# MotherboardRev1.net
KiCad netlist of a schematic drawn in EAGLE
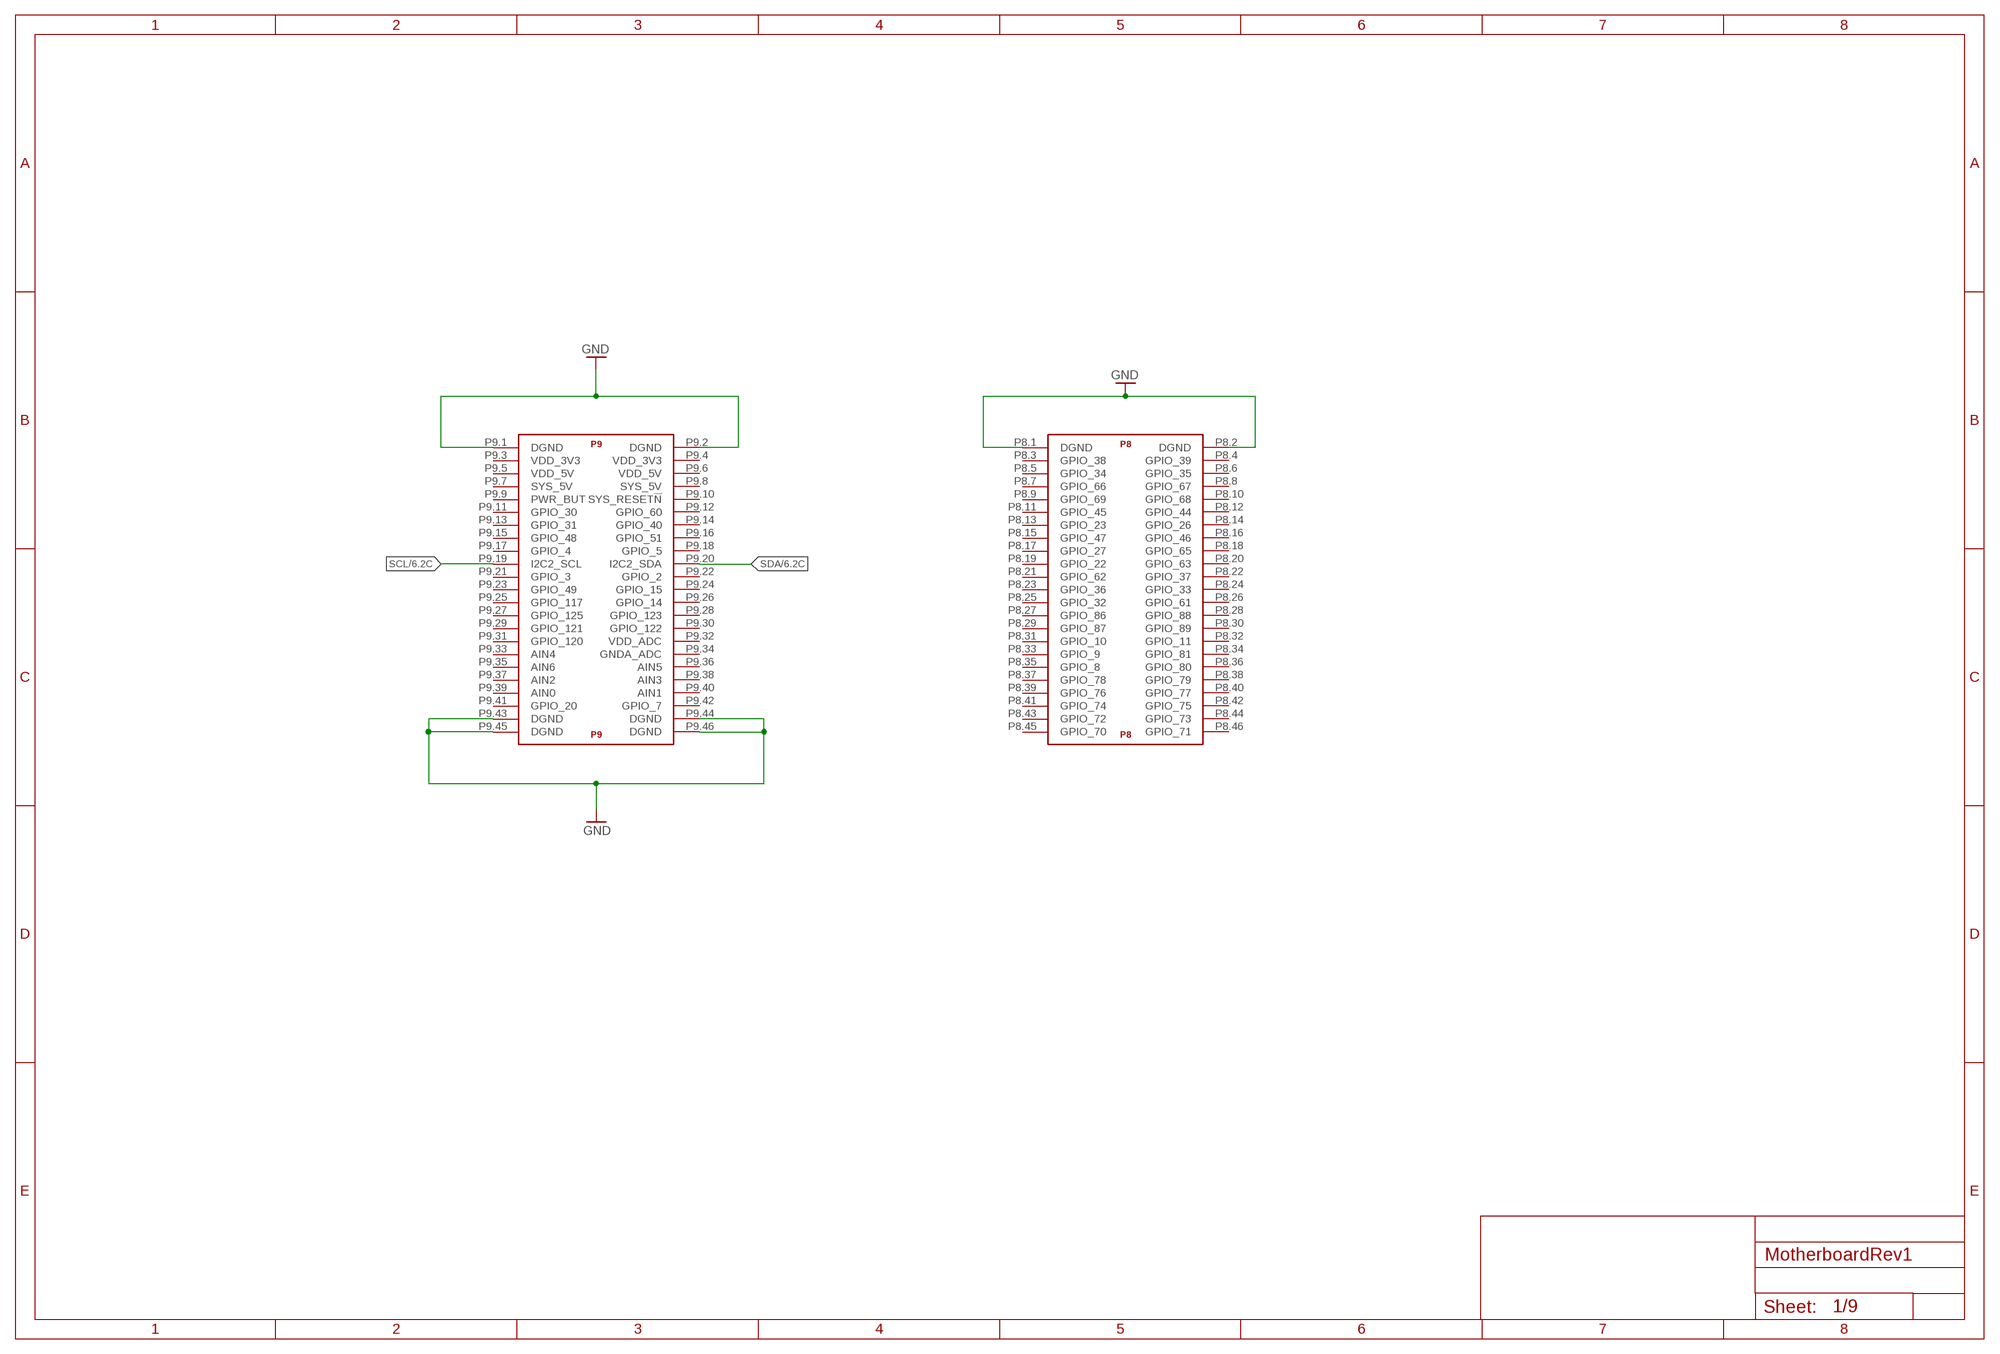
[diagram p0: schematic, sheet 1]
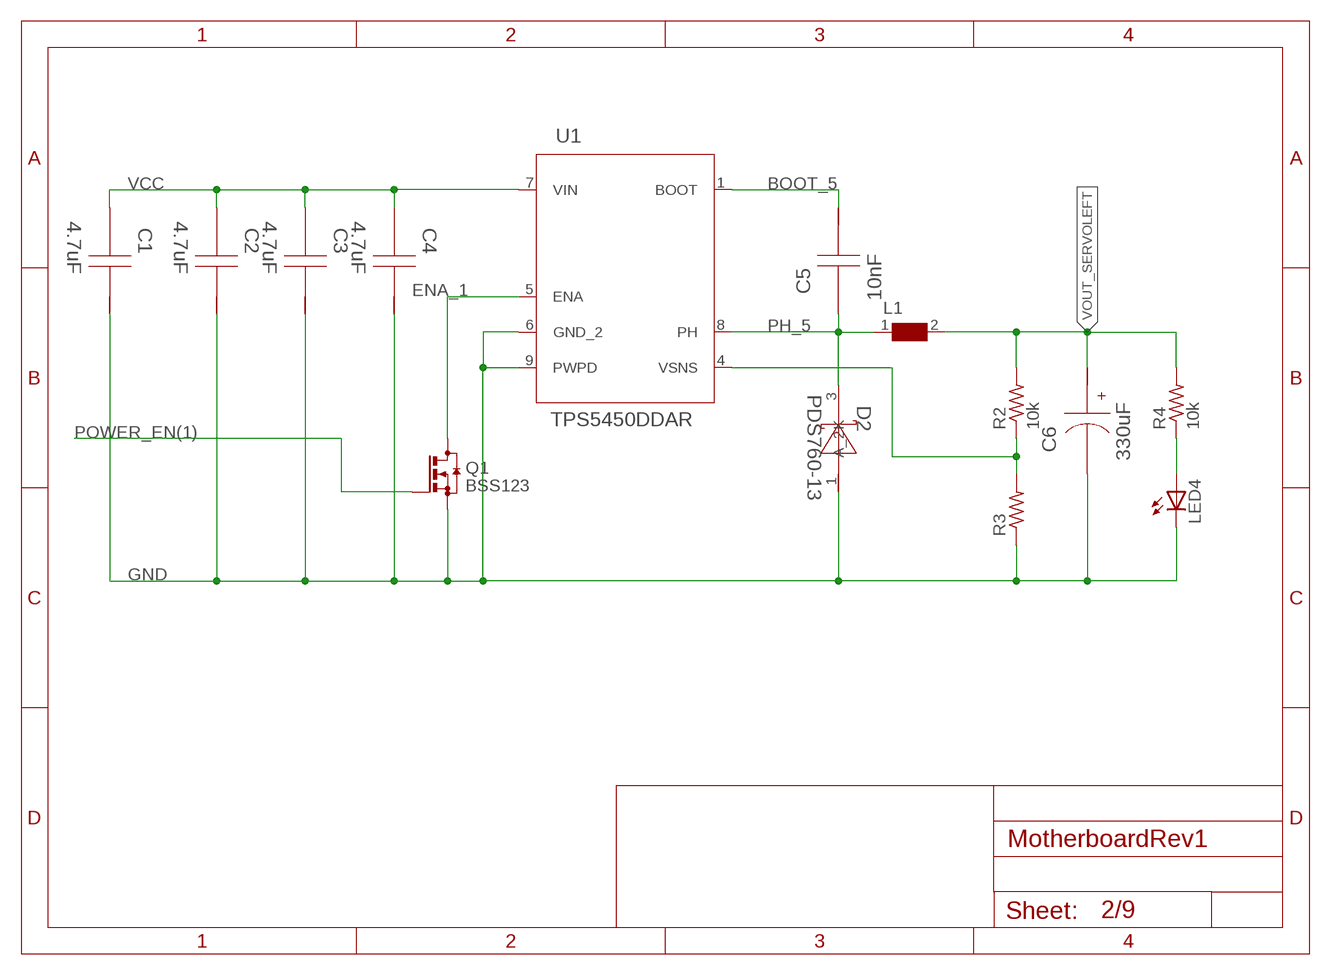
[diagram p1: schematic, sheet 2]
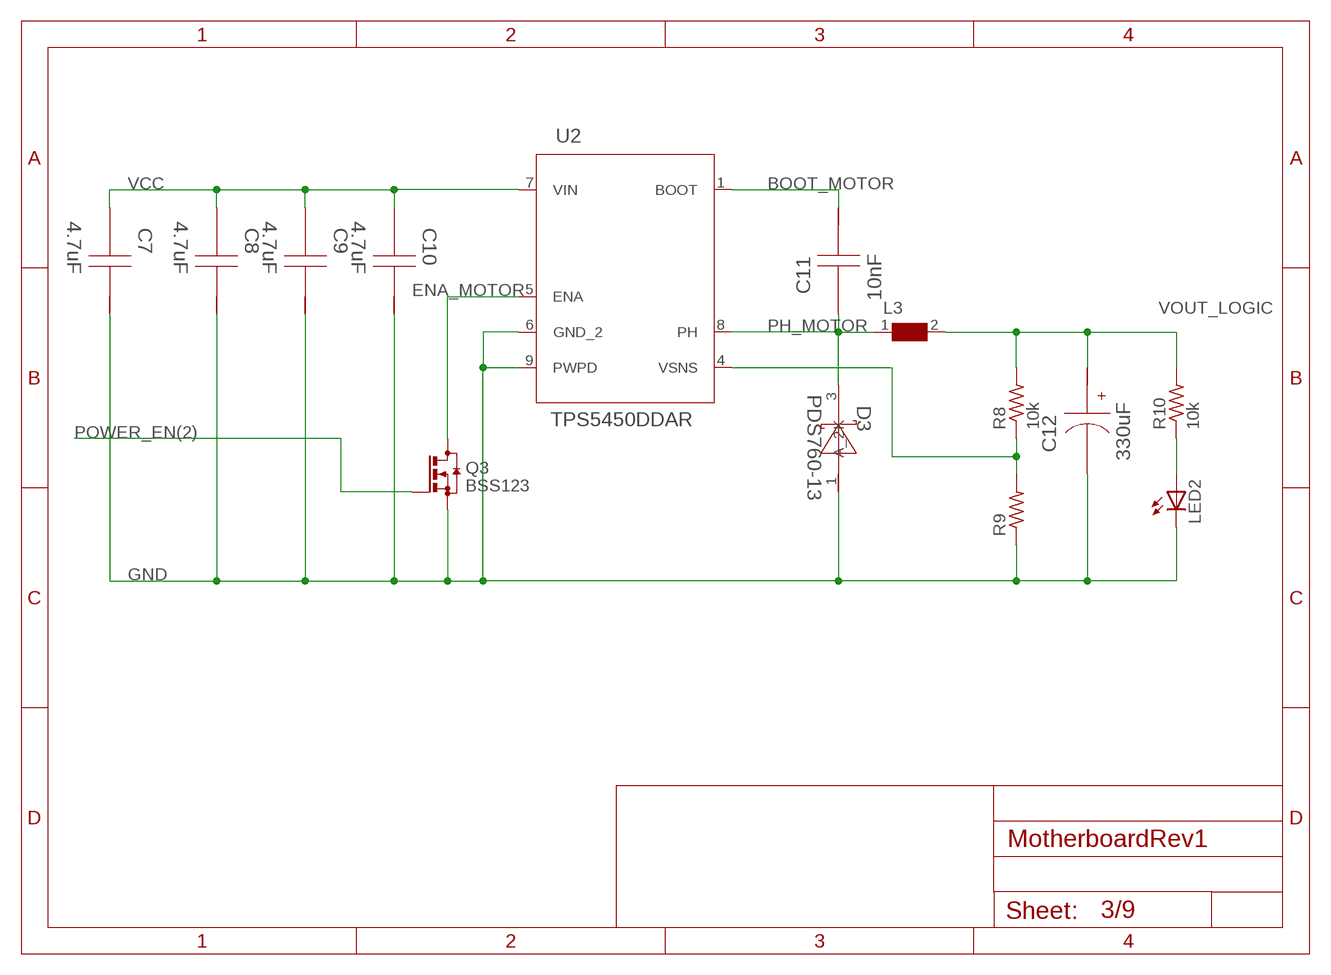
[diagram p2: schematic, sheet 3]
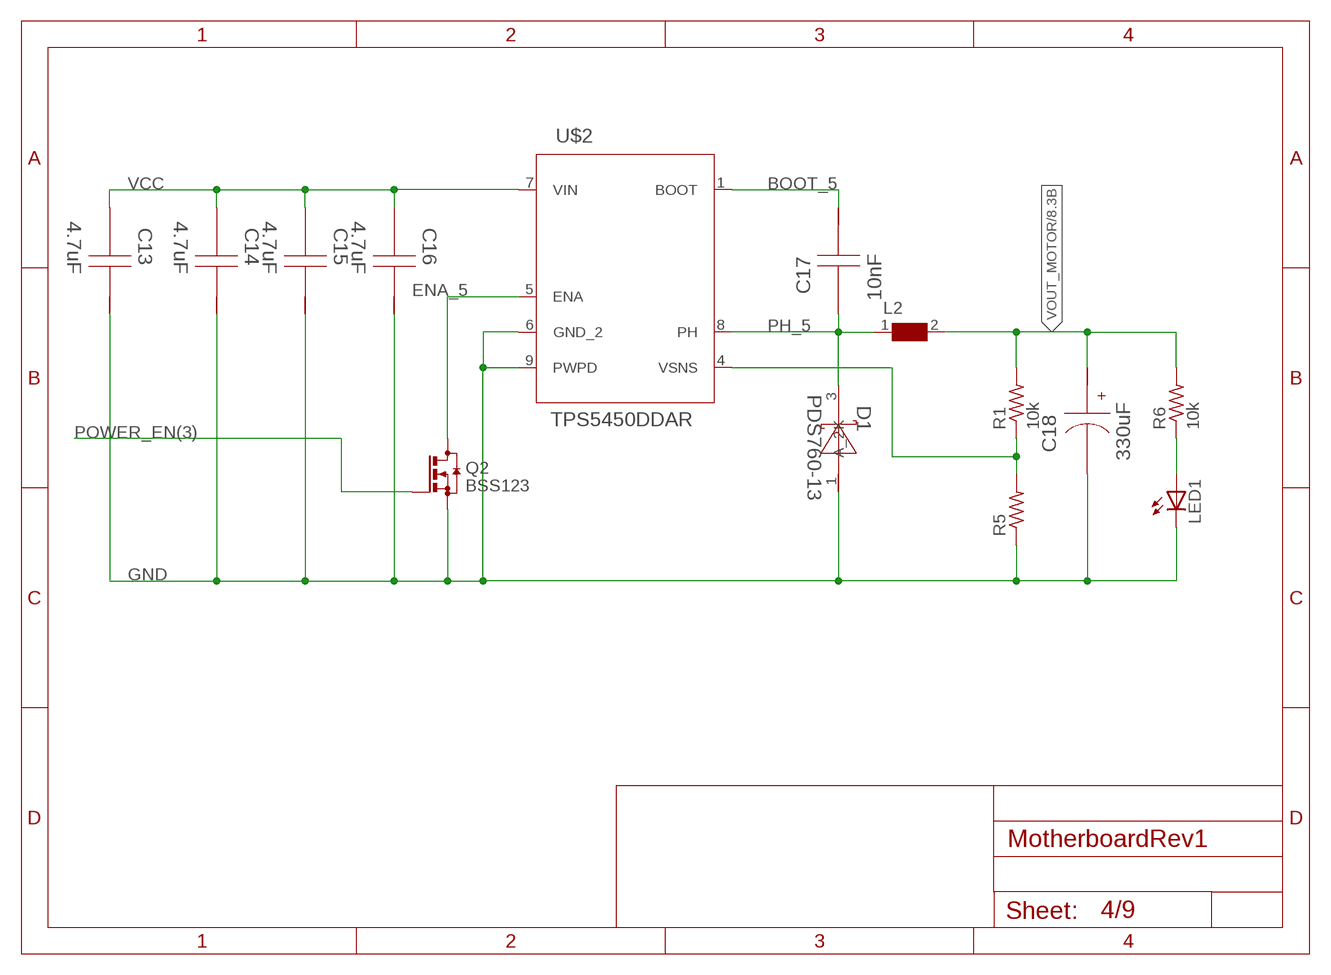
[diagram p3: schematic, sheet 4]
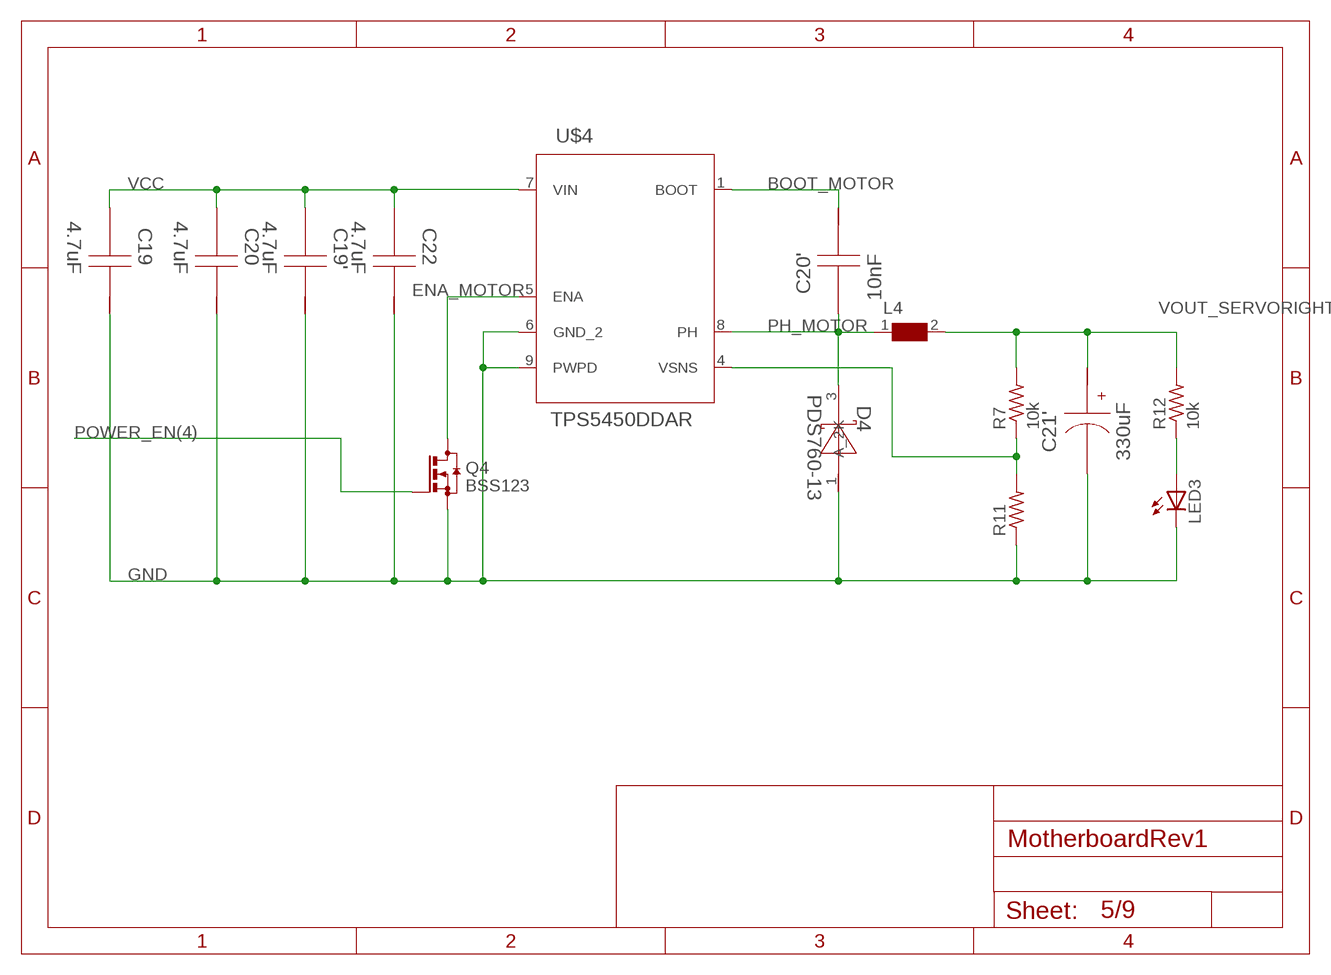
[diagram p4: schematic, sheet 5]
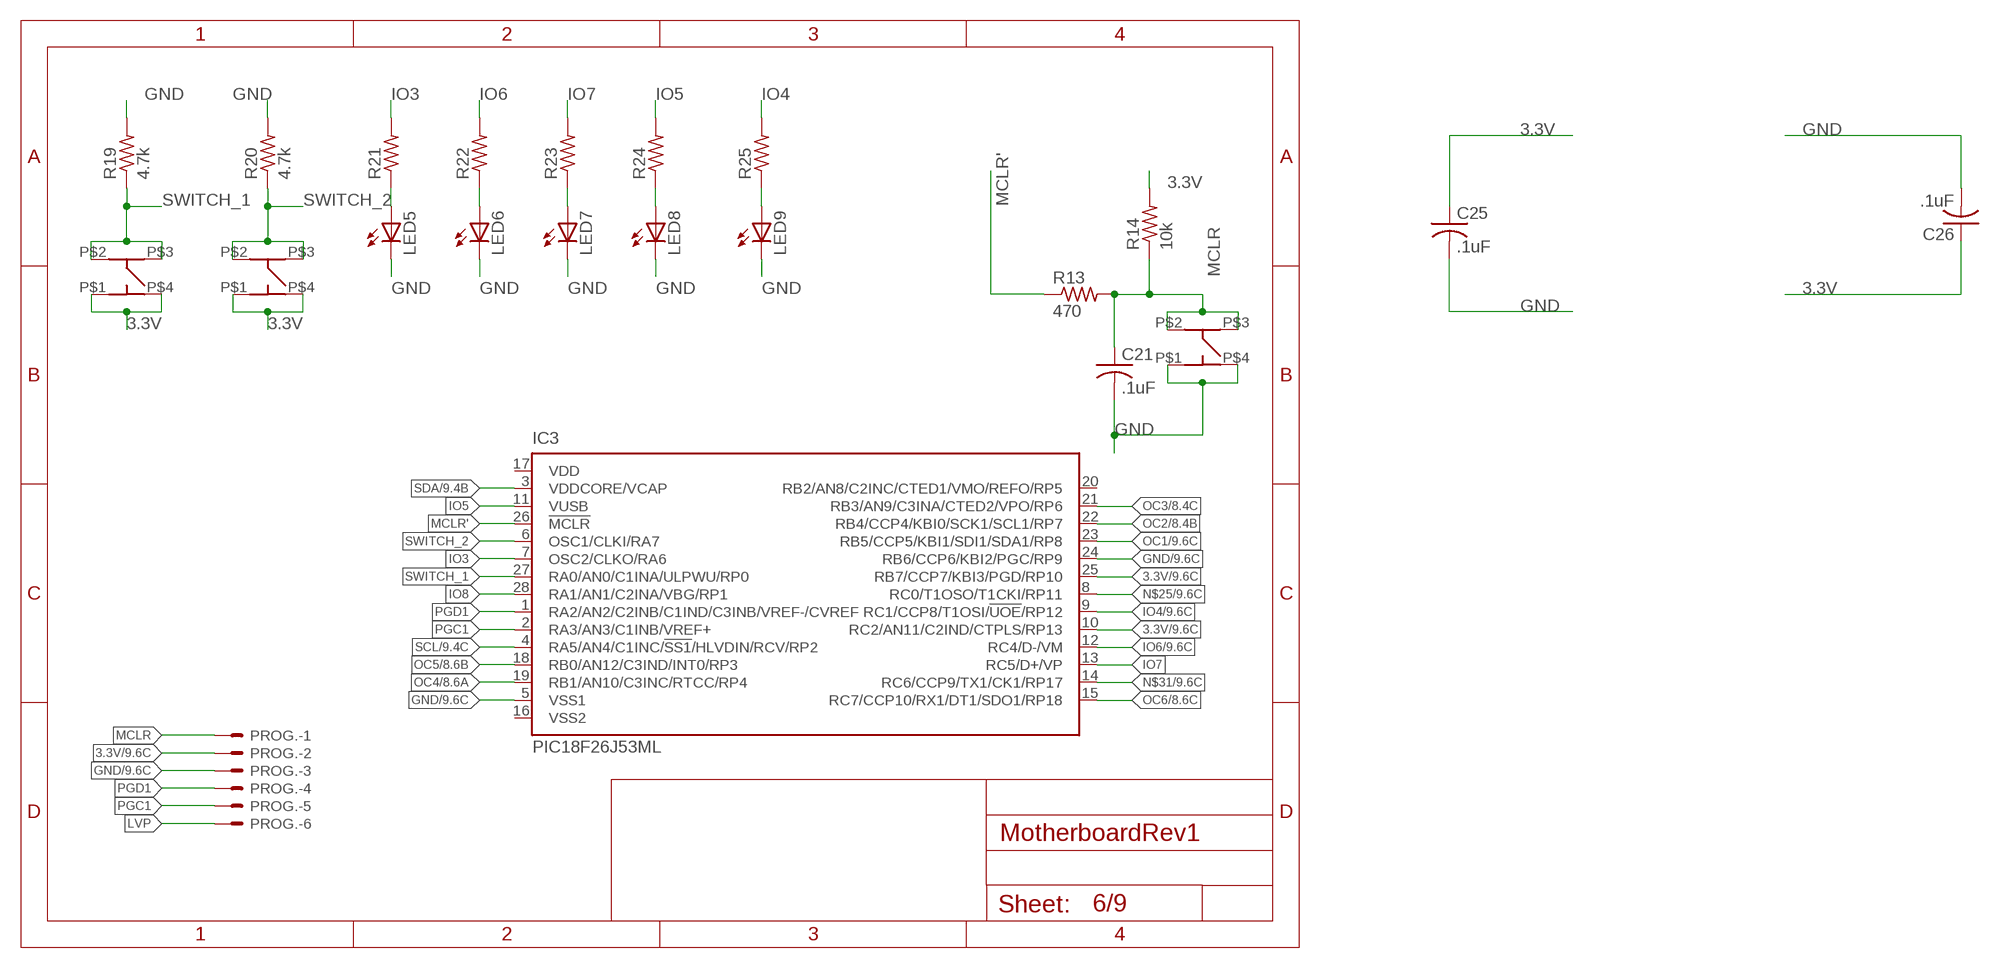
[diagram p5: schematic, sheet 6]
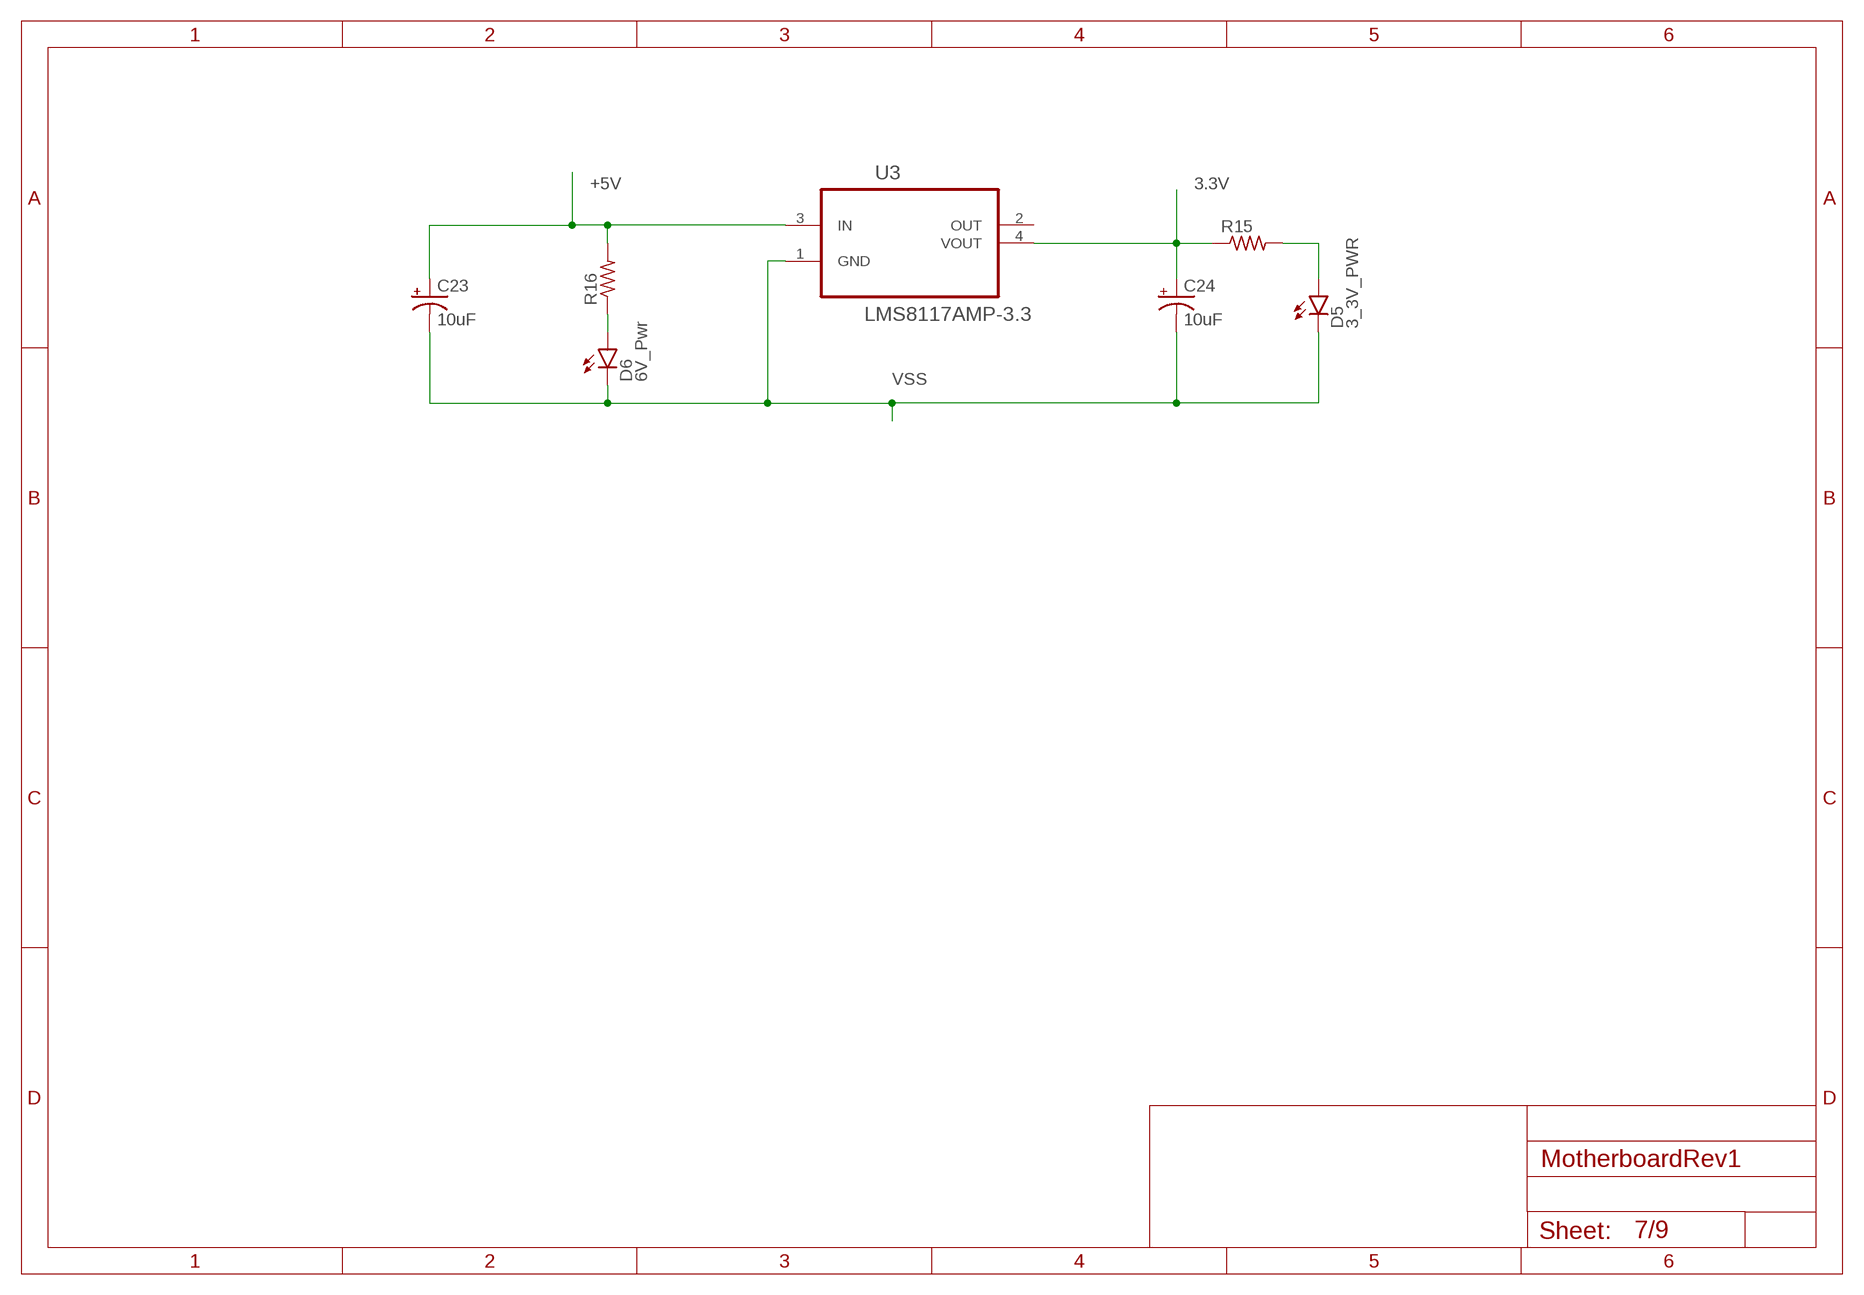
[diagram p6: schematic, sheet 7]
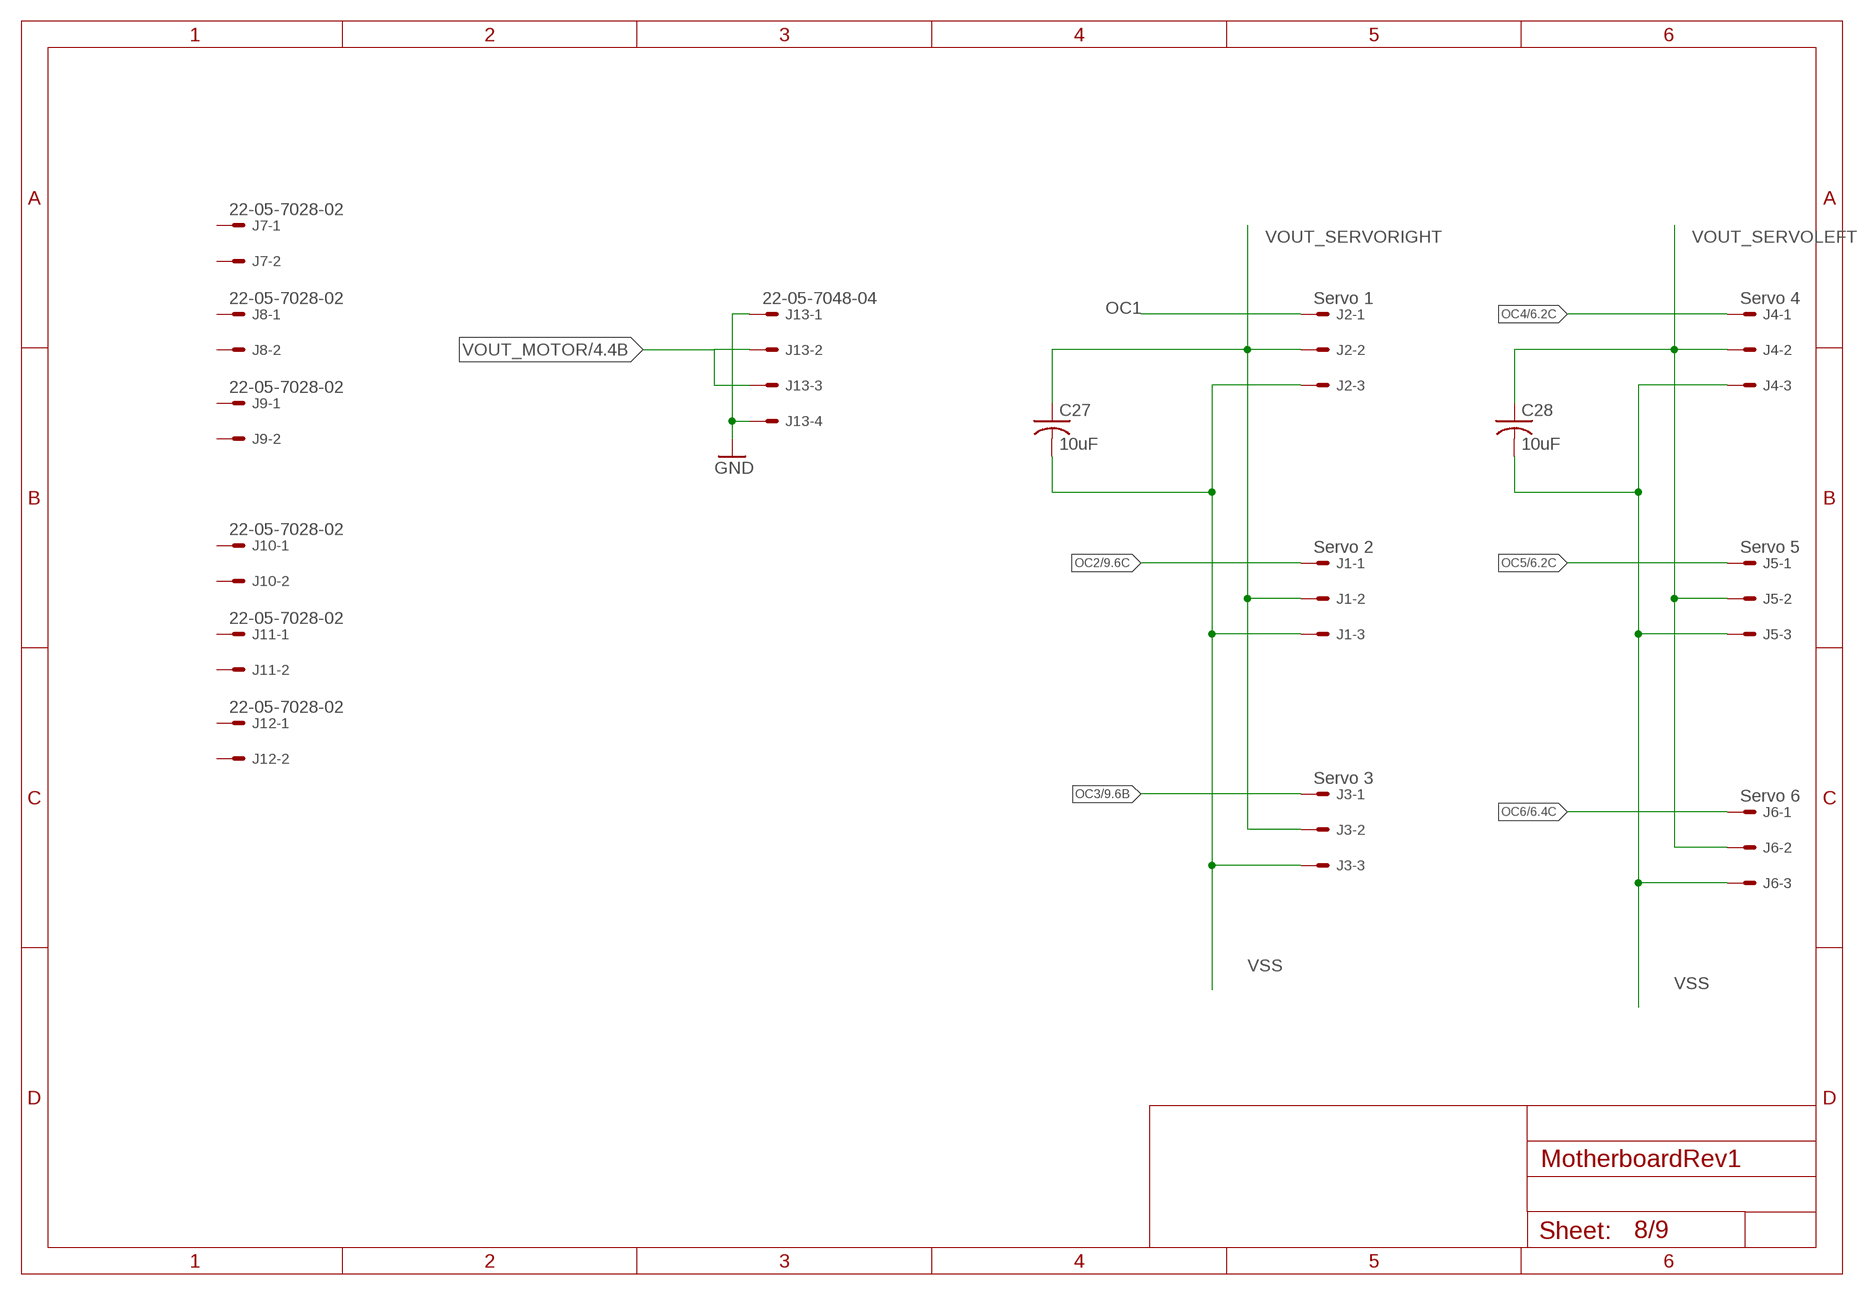
[diagram p7: schematic, sheet 8]
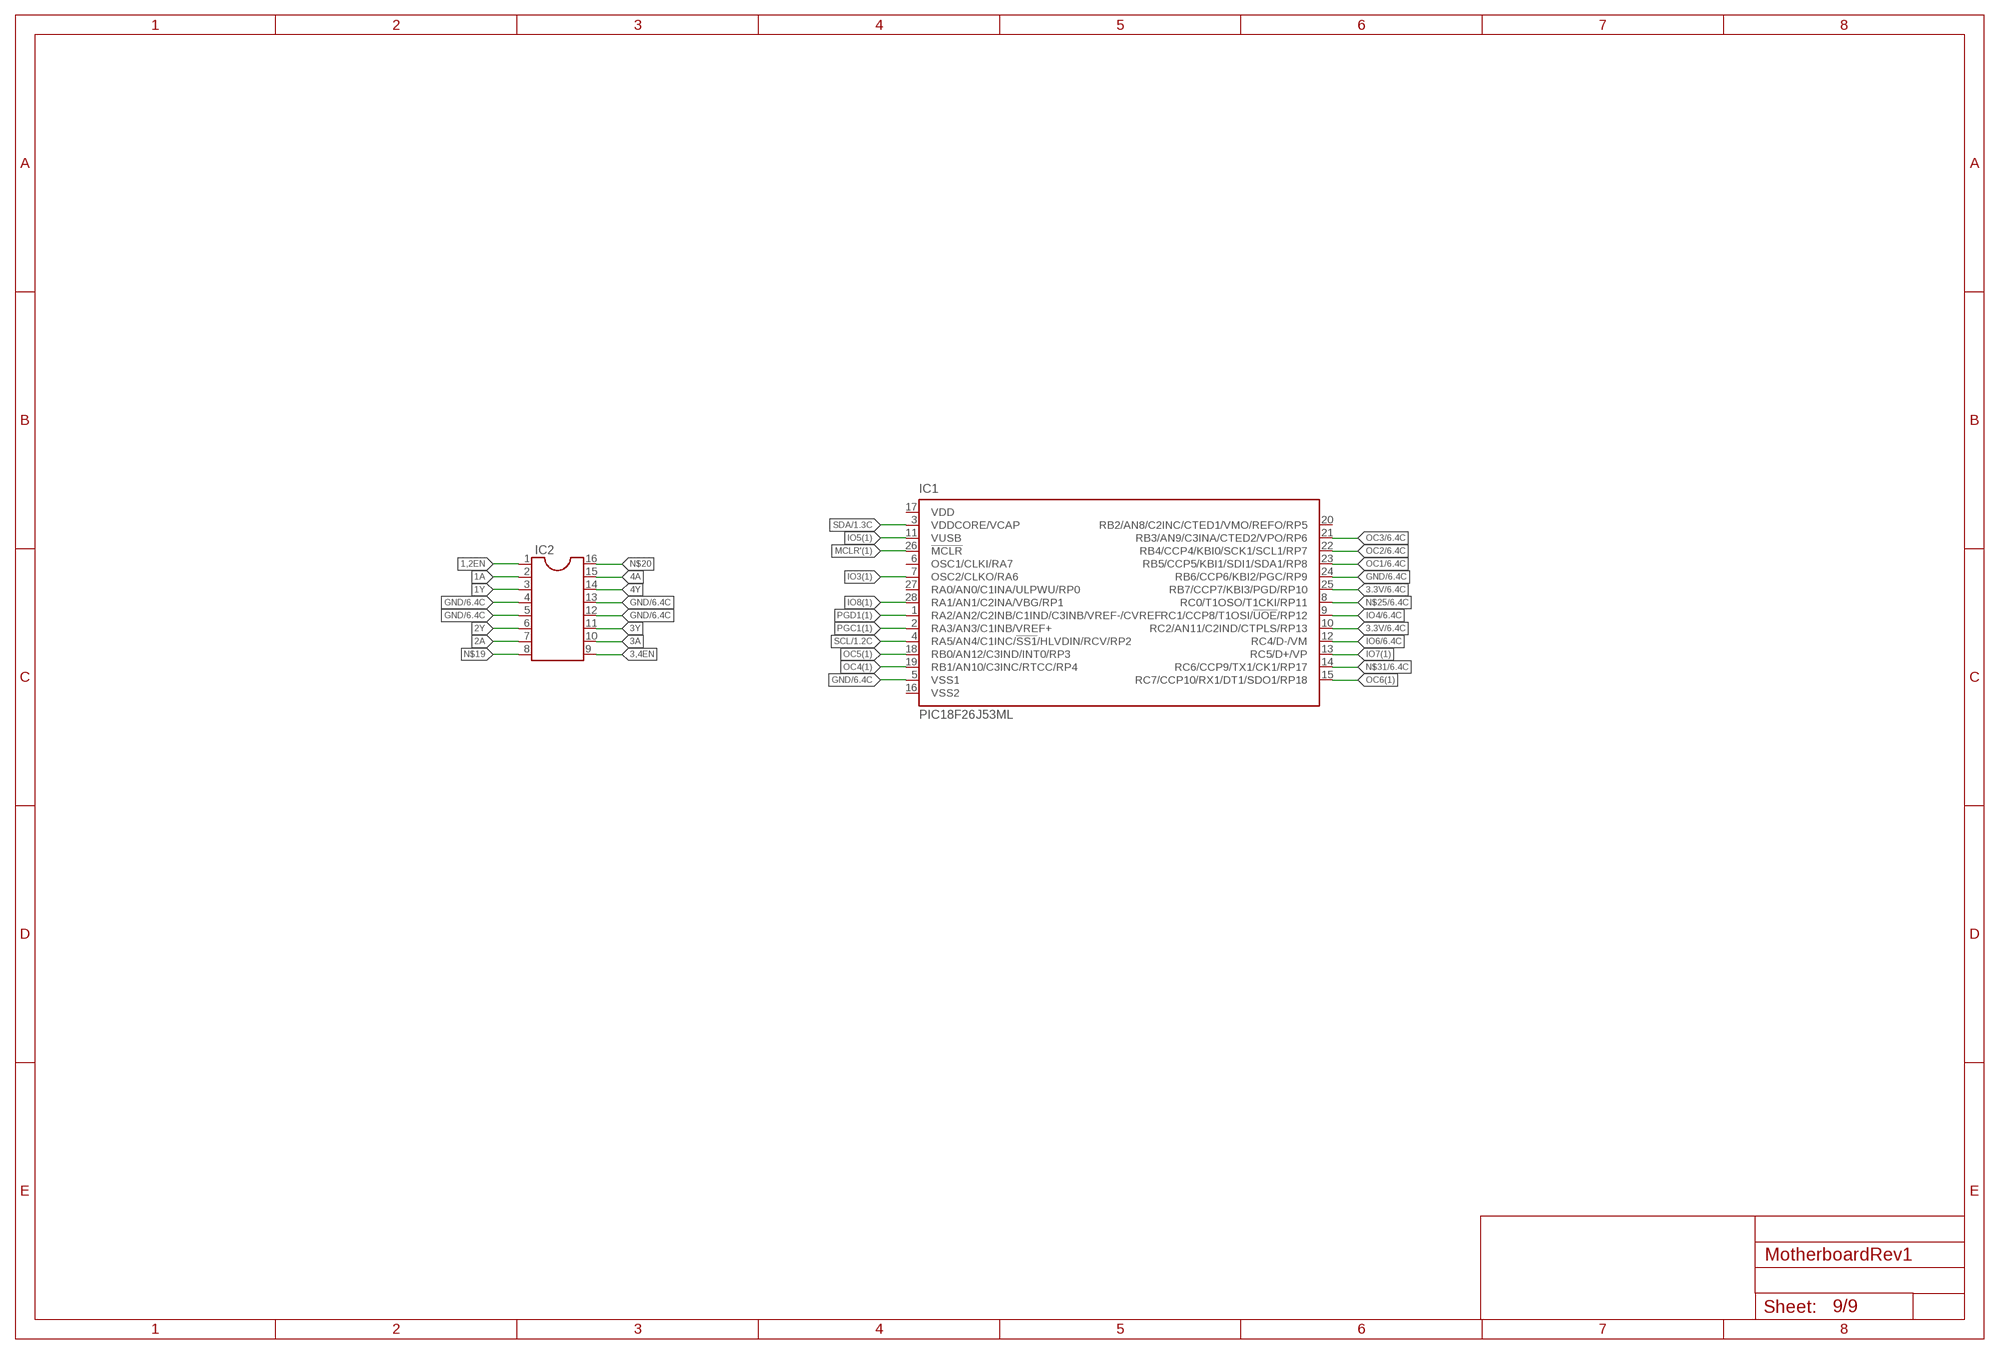
[diagram p8: schematic, sheet 9]

(export (version "E")
  (design (tool "Eeschema 10.0.6"))
  (components
    (comp (ref "C7")
      (value "4.7uF")
      (footprint "eagle-import:1206")
      (fields (field (name "MANUFACTURER_PART_NUMBER") "GRM31CR71H475KA12L"))
      (libsource (lib "eagle-import") (part "GRM31CR71H475KA12L"))
    )
    (comp (ref "C8")
      (value "4.7uF")
      (footprint "eagle-import:1206")
      (fields (field (name "MANUFACTURER_PART_NUMBER") "GRM31CR71H475KA12L"))
      (libsource (lib "eagle-import") (part "GRM31CR71H475KA12L"))
    )
    (comp (ref "C9")
      (value "4.7uF")
      (footprint "eagle-import:1206")
      (fields (field (name "MANUFACTURER_PART_NUMBER") "GRM31CR71H475KA12L"))
      (libsource (lib "eagle-import") (part "GRM31CR71H475KA12L"))
    )
    (comp (ref "C10")
      (value "4.7uF")
      (footprint "eagle-import:1206")
      (fields (field (name "MANUFACTURER_PART_NUMBER") "GRM31CR71H475KA12L"))
      (libsource (lib "eagle-import") (part "GRM31CR71H475KA12L"))
    )
    (comp (ref "C11")
      (value "10nF")
      (footprint "eagle-import:0805")
      (fields (field (name "MANUFACTURER_PART_NUMBER") "C0805C103K5RACTU"))
      (libsource (lib "eagle-import") (part "C0805C103K5RACTU"))
    )
    (comp (ref "C12")
      (value "330uF")
      (footprint "eagle-import:SM_RADIAL_10AMM")
      (fields (field (name "MANUFACTURER_PART_NUMBER") "10SVP330MX"))
      (libsource (lib "eagle-import") (part "10SVP330MX"))
    )
    (comp (ref "D3")
      (value "PDS760-13")
      (footprint "eagle-import:POWERDI5")
      (libsource (lib "eagle-import") (part "PDS760-13"))
    )
    (comp (ref "L3")
      (value "WE-HCC-7443331000_1090")
      (footprint "eagle-import:WE-HCC_1090")
      (fields (field (name "MPN") "7443331000"))
      (libsource (lib "eagle-import") (part "WE-HCC_1090-7443331000"))
    )
    (comp (ref "LED2")
      (value "LEDSML1206")
      (footprint "eagle-import:SML1206")
      (libsource (lib "eagle-import") (part "LEDSML1206"))
    )
    (comp (ref "Q3")
      (value "BSS123")
      (footprint "eagle-import:SOT23")
      (libsource (lib "eagle-import") (part "BSS123"))
    )
    (comp (ref "R8")
      (value "10k")
      (footprint "eagle-import:R1206")
      (libsource (lib "eagle-import") (part "R-US_R1206"))
    )
    (comp (ref "R9")
      (value "R-US_R1206")
      (footprint "eagle-import:R1206")
      (libsource (lib "eagle-import") (part "R-US_R1206"))
    )
    (comp (ref "R10")
      (value "10k")
      (footprint "eagle-import:R1206")
      (libsource (lib "eagle-import") (part "R-US_R1206"))
    )
    (comp (ref "U2")
      (value "TPS5450DDAR")
      (footprint "eagle-import:R-PDSO-G8")
      (fields (field (name "MANUFACTURER_PART_NUMBER") "TPS5450DDA"))
      (libsource (lib "eagle-import") (part "TPS5450DDAR"))
    )
    (comp (ref "C27")
      (value "10uF")
      (footprint "eagle-import:C0805")
      (libsource (lib "eagle-import") (part "C-USC0805"))
    )
    (comp (ref "C28")
      (value "10uF")
      (footprint "eagle-import:C0805")
      (libsource (lib "eagle-import") (part "C-USC0805"))
    )
    (comp (ref "J1")
      (value "Servo 2")
      (footprint "eagle-import:7395-03")
      (libsource (lib "eagle-import") (part "22-?-0305-7038"))
    )
    (comp (ref "J2")
      (value "Servo 1")
      (footprint "eagle-import:7395-03")
      (libsource (lib "eagle-import") (part "22-?-0305-7038"))
    )
    (comp (ref "J3")
      (value "Servo 3")
      (footprint "eagle-import:7395-03")
      (libsource (lib "eagle-import") (part "22-?-0305-7038"))
    )
    (comp (ref "J4")
      (value "Servo 4")
      (footprint "eagle-import:7395-03")
      (libsource (lib "eagle-import") (part "22-?-0305-7038"))
    )
    (comp (ref "J5")
      (value "Servo 5")
      (footprint "eagle-import:7395-03")
      (libsource (lib "eagle-import") (part "22-?-0305-7038"))
    )
    (comp (ref "J6")
      (value "Servo 6")
      (footprint "eagle-import:7395-03")
      (libsource (lib "eagle-import") (part "22-?-0305-7038"))
    )
    (comp (ref "J7")
      (value "22-05-7028-02")
      (footprint "eagle-import:7395-02")
      (libsource (lib "eagle-import") (part "22-?-0205-7028"))
    )
    (comp (ref "J8")
      (value "22-05-7028-02")
      (footprint "eagle-import:7395-02")
      (libsource (lib "eagle-import") (part "22-?-0205-7028"))
    )
    (comp (ref "J9")
      (value "22-05-7028-02")
      (footprint "eagle-import:7395-02")
      (libsource (lib "eagle-import") (part "22-?-0205-7028"))
    )
    (comp (ref "J10")
      (value "22-05-7028-02")
      (footprint "eagle-import:7395-02")
      (libsource (lib "eagle-import") (part "22-?-0205-7028"))
    )
    (comp (ref "J11")
      (value "22-05-7028-02")
      (footprint "eagle-import:7395-02")
      (libsource (lib "eagle-import") (part "22-?-0205-7028"))
    )
    (comp (ref "J12")
      (value "22-05-7028-02")
      (footprint "eagle-import:7395-02")
      (libsource (lib "eagle-import") (part "22-?-0205-7028"))
    )
    (comp (ref "J13")
      (value "22-05-7048-04")
      (footprint "eagle-import:7395-04")
      (libsource (lib "eagle-import") (part "22-?-0405-7048"))
    )
    (comp (ref "C23")
      (value "10uF")
      (footprint "eagle-import:EIA3216")
      (libsource (lib "eagle-import") (part "10UF-16V-10%(TANT)"))
    )
    (comp (ref "C24")
      (value "10uF")
      (footprint "eagle-import:EIA3216")
      (libsource (lib "eagle-import") (part "10UF-16V-10%(TANT)"))
    )
    (comp (ref "D5")
      (value "3_3V_PWR")
      (footprint "eagle-import:FKIT-LED-1206")
      (libsource (lib "eagle-import") (part "LED-FKIT-1206"))
    )
    (comp (ref "D6")
      (value "6V_Pwr")
      (footprint "eagle-import:FKIT-LED-1206")
      (libsource (lib "eagle-import") (part "LED-FKIT-1206"))
    )
    (comp (ref "R15")
      (value "R-US_R0805W")
      (footprint "eagle-import:R0805W")
      (libsource (lib "eagle-import") (part "R-US_R0805W"))
    )
    (comp (ref "R16")
      (value "R-US_R0805W")
      (footprint "eagle-import:R0805W")
      (libsource (lib "eagle-import") (part "R-US_R0805W"))
    )
    (comp (ref "U3")
      (value "LMS8117AMP-3.3")
      (footprint "eagle-import:SOT230P696X180-4N")
      (libsource (lib "eagle-import") (part "LMS8117AMP-3.3"))
    )
    (comp (ref "C21")
      (value ".1uF")
      (footprint "eagle-import:C0805")
      (libsource (lib "eagle-import") (part "C-USC0805"))
    )
    (comp (ref "C25")
      (value ".1uF")
      (footprint "eagle-import:C0805")
      (libsource (lib "eagle-import") (part "C-USC0805"))
    )
    (comp (ref "C26")
      (value ".1uF")
      (footprint "eagle-import:C0805")
      (libsource (lib "eagle-import") (part "C-USC0805"))
    )
    (comp (ref "IC3")
      (value "PIC18F26J53ML")
      (footprint "eagle-import:QFN28-ML_6X6MM")
      (fields (field (name "MPN") "PIC18F26J53-I/ML"))
      (libsource (lib "eagle-import") (part "PIC18F2J53ML6"))
    )
    (comp (ref "LED5")
      (value "LED_LEDCHIPLED_1206")
      (footprint "eagle-import:LED_CHIPLED_1206")
      (libsource (lib "eagle-import") (part "LED_LEDCHIPLED_1206"))
    )
    (comp (ref "LED6")
      (value "LED_LEDCHIPLED_1206")
      (footprint "eagle-import:LED_CHIPLED_1206")
      (libsource (lib "eagle-import") (part "LED_LEDCHIPLED_1206"))
    )
    (comp (ref "LED7")
      (value "LED_LEDCHIPLED_1206")
      (footprint "eagle-import:LED_CHIPLED_1206")
      (libsource (lib "eagle-import") (part "LED_LEDCHIPLED_1206"))
    )
    (comp (ref "LED8")
      (value "LED_LEDCHIPLED_1206")
      (footprint "eagle-import:LED_CHIPLED_1206")
      (libsource (lib "eagle-import") (part "LED_LEDCHIPLED_1206"))
    )
    (comp (ref "LED9")
      (value "LED_LEDCHIPLED_1206")
      (footprint "eagle-import:LED_CHIPLED_1206")
      (libsource (lib "eagle-import") (part "LED_LEDCHIPLED_1206"))
    )
    (comp (ref "PROG.")
      (value "22-23-2061")
      (footprint "eagle-import:22-23-2061")
      (fields (field (name "MF") "MOLEX"))
      (libsource (lib "eagle-import") (part "22-23-2061"))
    )
    (comp (ref "R13")
      (value "470")
      (footprint "eagle-import:R0805")
      (libsource (lib "eagle-import") (part "R-US_R0805"))
    )
    (comp (ref "R14")
      (value "10k")
      (footprint "eagle-import:R0805")
      (libsource (lib "eagle-import") (part "R-US_R0805"))
    )
    (comp (ref "R19")
      (value "4.7k")
      (footprint "eagle-import:R0805")
      (libsource (lib "eagle-import") (part "R-US_R0805"))
    )
    (comp (ref "R20")
      (value "4.7k")
      (footprint "eagle-import:R0805")
      (libsource (lib "eagle-import") (part "R-US_R0805"))
    )
    (comp (ref "R21")
      (value "R-US_M0805")
      (footprint "eagle-import:M0805")
      (libsource (lib "eagle-import") (part "R-US_M0805"))
    )
    (comp (ref "R22")
      (value "R-US_M0805")
      (footprint "eagle-import:M0805")
      (libsource (lib "eagle-import") (part "R-US_M0805"))
    )
    (comp (ref "R23")
      (value "R-US_M0805")
      (footprint "eagle-import:M0805")
      (libsource (lib "eagle-import") (part "R-US_M0805"))
    )
    (comp (ref "R24")
      (value "R-US_M0805")
      (footprint "eagle-import:M0805")
      (libsource (lib "eagle-import") (part "R-US_M0805"))
    )
    (comp (ref "R25")
      (value "R-US_M0805")
      (footprint "eagle-import:M0805")
      (libsource (lib "eagle-import") (part "R-US_M0805"))
    )
    (comp (ref "U$5")
      (value "Switch3")
      (footprint "eagle-import:MC32882_FINAL")
      (libsource (lib "eagle-import") (part "MC32882_SW"))
    )
    (comp (ref "U$6")
      (value "Switch1")
      (footprint "eagle-import:MC32882_FINAL")
      (libsource (lib "eagle-import") (part "MC32882_SW"))
    )
    (comp (ref "U$7")
      (value "Switch2")
      (footprint "eagle-import:MC32882_FINAL")
      (libsource (lib "eagle-import") (part "MC32882_SW"))
    )
    (comp (ref "U$1")
      (value "BEAGLE_BONE_BLACK_CAPE")
      (footprint "eagle-import:BEAGLE_BONE_BLACK_CAPE")
      (libsource (lib "eagle-import") (part "BEAGLE_BONE_BLACK_CAPE"))
    )
    (comp (ref "C19")
      (value "4.7uF")
      (footprint "eagle-import:1206")
      (fields (field (name "MANUFACTURER_PART_NUMBER") "GRM31CR71H475KA12L"))
      (libsource (lib "eagle-import") (part "GRM31CR71H475KA12L"))
    )
    (comp (ref "C19'")
      (value "4.7uF")
      (footprint "eagle-import:1206")
      (fields (field (name "MANUFACTURER_PART_NUMBER") "GRM31CR71H475KA12L"))
      (libsource (lib "eagle-import") (part "GRM31CR71H475KA12L"))
    )
    (comp (ref "C20")
      (value "4.7uF")
      (footprint "eagle-import:1206")
      (fields (field (name "MANUFACTURER_PART_NUMBER") "GRM31CR71H475KA12L"))
      (libsource (lib "eagle-import") (part "GRM31CR71H475KA12L"))
    )
    (comp (ref "C20'")
      (value "10nF")
      (footprint "eagle-import:0805")
      (fields (field (name "MANUFACTURER_PART_NUMBER") "C0805C103K5RACTU"))
      (libsource (lib "eagle-import") (part "C0805C103K5RACTU"))
    )
    (comp (ref "C21'")
      (value "330uF")
      (footprint "eagle-import:SM_RADIAL_10AMM")
      (fields (field (name "MANUFACTURER_PART_NUMBER") "10SVP330MX"))
      (libsource (lib "eagle-import") (part "10SVP330MX"))
    )
    (comp (ref "C22")
      (value "4.7uF")
      (footprint "eagle-import:1206")
      (fields (field (name "MANUFACTURER_PART_NUMBER") "GRM31CR71H475KA12L"))
      (libsource (lib "eagle-import") (part "GRM31CR71H475KA12L"))
    )
    (comp (ref "D4")
      (value "PDS760-13")
      (footprint "eagle-import:POWERDI5")
      (libsource (lib "eagle-import") (part "PDS760-13"))
    )
    (comp (ref "L4")
      (value "WE-HCC-7443331000_1090")
      (footprint "eagle-import:WE-HCC_1090")
      (fields (field (name "MPN") "7443331000"))
      (libsource (lib "eagle-import") (part "WE-HCC_1090-7443331000"))
    )
    (comp (ref "LED3")
      (value "LEDSML1206")
      (footprint "eagle-import:SML1206")
      (libsource (lib "eagle-import") (part "LEDSML1206"))
    )
    (comp (ref "Q4")
      (value "BSS123")
      (footprint "eagle-import:SOT23")
      (libsource (lib "eagle-import") (part "BSS123"))
    )
    (comp (ref "R7")
      (value "10k")
      (footprint "eagle-import:R1206")
      (libsource (lib "eagle-import") (part "R-US_R1206"))
    )
    (comp (ref "R11")
      (value "R-US_R1206")
      (footprint "eagle-import:R1206")
      (libsource (lib "eagle-import") (part "R-US_R1206"))
    )
    (comp (ref "R12")
      (value "10k")
      (footprint "eagle-import:R1206")
      (libsource (lib "eagle-import") (part "R-US_R1206"))
    )
    (comp (ref "U$4")
      (value "TPS5450DDAR")
      (footprint "eagle-import:R-PDSO-G8")
      (fields (field (name "MANUFACTURER_PART_NUMBER") "TPS5450DDA"))
      (libsource (lib "eagle-import") (part "TPS5450DDAR"))
    )
    (comp (ref "IC1")
      (value "PIC18F26J53ML")
      (footprint "eagle-import:QFN28-ML_6X6MM")
      (fields (field (name "MPN") "PIC18F26J53-I/ML"))
      (libsource (lib "eagle-import") (part "PIC18F2J53ML6"))
    )
    (comp (ref "IC2")
      (value "DIL16")
      (footprint "eagle-import:DIL16")
      (libsource (lib "eagle-import") (part "DIL16"))
    )
    (comp (ref "C13")
      (value "4.7uF")
      (footprint "eagle-import:1206")
      (fields (field (name "MANUFACTURER_PART_NUMBER") "GRM31CR71H475KA12L"))
      (libsource (lib "eagle-import") (part "GRM31CR71H475KA12L"))
    )
    (comp (ref "C14")
      (value "4.7uF")
      (footprint "eagle-import:1206")
      (fields (field (name "MANUFACTURER_PART_NUMBER") "GRM31CR71H475KA12L"))
      (libsource (lib "eagle-import") (part "GRM31CR71H475KA12L"))
    )
    (comp (ref "C15")
      (value "4.7uF")
      (footprint "eagle-import:1206")
      (fields (field (name "MANUFACTURER_PART_NUMBER") "GRM31CR71H475KA12L"))
      (libsource (lib "eagle-import") (part "GRM31CR71H475KA12L"))
    )
    (comp (ref "C16")
      (value "4.7uF")
      (footprint "eagle-import:1206")
      (fields (field (name "MANUFACTURER_PART_NUMBER") "GRM31CR71H475KA12L"))
      (libsource (lib "eagle-import") (part "GRM31CR71H475KA12L"))
    )
    (comp (ref "C17")
      (value "10nF")
      (footprint "eagle-import:0805")
      (fields (field (name "MANUFACTURER_PART_NUMBER") "C0805C103K5RACTU"))
      (libsource (lib "eagle-import") (part "C0805C103K5RACTU"))
    )
    (comp (ref "C18")
      (value "330uF")
      (footprint "eagle-import:SM_RADIAL_10AMM")
      (fields (field (name "MANUFACTURER_PART_NUMBER") "10SVP330MX"))
      (libsource (lib "eagle-import") (part "10SVP330MX"))
    )
    (comp (ref "D1")
      (value "PDS760-13")
      (footprint "eagle-import:POWERDI5")
      (libsource (lib "eagle-import") (part "PDS760-13"))
    )
    (comp (ref "L2")
      (value "WE-HCC-7443331000_1090")
      (footprint "eagle-import:WE-HCC_1090")
      (fields (field (name "MPN") "7443331000"))
      (libsource (lib "eagle-import") (part "WE-HCC_1090-7443331000"))
    )
    (comp (ref "LED1")
      (value "LEDSML1206")
      (footprint "eagle-import:SML1206")
      (libsource (lib "eagle-import") (part "LEDSML1206"))
    )
    (comp (ref "Q2")
      (value "BSS123")
      (footprint "eagle-import:SOT23")
      (libsource (lib "eagle-import") (part "BSS123"))
    )
    (comp (ref "R1")
      (value "10k")
      (footprint "eagle-import:R1206")
      (libsource (lib "eagle-import") (part "R-US_R1206"))
    )
    (comp (ref "R5")
      (value "R-US_R1206")
      (footprint "eagle-import:R1206")
      (libsource (lib "eagle-import") (part "R-US_R1206"))
    )
    (comp (ref "R6")
      (value "10k")
      (footprint "eagle-import:R1206")
      (libsource (lib "eagle-import") (part "R-US_R1206"))
    )
    (comp (ref "U$2")
      (value "TPS5450DDAR")
      (footprint "eagle-import:R-PDSO-G8")
      (fields (field (name "MANUFACTURER_PART_NUMBER") "TPS5450DDA"))
      (libsource (lib "eagle-import") (part "TPS5450DDAR"))
    )
    (comp (ref "C1")
      (value "4.7uF")
      (footprint "eagle-import:1206")
      (fields (field (name "MANUFACTURER_PART_NUMBER") "GRM31CR71H475KA12L"))
      (libsource (lib "eagle-import") (part "GRM31CR71H475KA12L"))
    )
    (comp (ref "C2")
      (value "4.7uF")
      (footprint "eagle-import:1206")
      (fields (field (name "MANUFACTURER_PART_NUMBER") "GRM31CR71H475KA12L"))
      (libsource (lib "eagle-import") (part "GRM31CR71H475KA12L"))
    )
    (comp (ref "C3")
      (value "4.7uF")
      (footprint "eagle-import:1206")
      (fields (field (name "MANUFACTURER_PART_NUMBER") "GRM31CR71H475KA12L"))
      (libsource (lib "eagle-import") (part "GRM31CR71H475KA12L"))
    )
    (comp (ref "C4")
      (value "4.7uF")
      (footprint "eagle-import:1206")
      (fields (field (name "MANUFACTURER_PART_NUMBER") "GRM31CR71H475KA12L"))
      (libsource (lib "eagle-import") (part "GRM31CR71H475KA12L"))
    )
    (comp (ref "C5")
      (value "10nF")
      (footprint "eagle-import:0805")
      (fields (field (name "MANUFACTURER_PART_NUMBER") "C0805C103K5RACTU"))
      (libsource (lib "eagle-import") (part "C0805C103K5RACTU"))
    )
    (comp (ref "C6")
      (value "330uF")
      (footprint "eagle-import:SM_RADIAL_10AMM")
      (fields (field (name "MANUFACTURER_PART_NUMBER") "10SVP330MX"))
      (libsource (lib "eagle-import") (part "10SVP330MX"))
    )
    (comp (ref "D2")
      (value "PDS760-13")
      (footprint "eagle-import:POWERDI5")
      (libsource (lib "eagle-import") (part "PDS760-13"))
    )
    (comp (ref "L1")
      (value "WE-HCC-7443331000_1090")
      (footprint "eagle-import:WE-HCC_1090")
      (fields (field (name "MPN") "7443331000"))
      (libsource (lib "eagle-import") (part "WE-HCC_1090-7443331000"))
    )
    (comp (ref "LED4")
      (value "LEDSML1206")
      (footprint "eagle-import:SML1206")
      (libsource (lib "eagle-import") (part "LEDSML1206"))
    )
    (comp (ref "Q1")
      (value "BSS123")
      (footprint "eagle-import:SOT23")
      (libsource (lib "eagle-import") (part "BSS123"))
    )
    (comp (ref "R2")
      (value "10k")
      (footprint "eagle-import:R1206")
      (libsource (lib "eagle-import") (part "R-US_R1206"))
    )
    (comp (ref "R3")
      (value "R-US_R1206")
      (footprint "eagle-import:R1206")
      (libsource (lib "eagle-import") (part "R-US_R1206"))
    )
    (comp (ref "R4")
      (value "10k")
      (footprint "eagle-import:R1206")
      (libsource (lib "eagle-import") (part "R-US_R1206"))
    )
    (comp (ref "U1")
      (value "TPS5450DDAR")
      (footprint "eagle-import:R-PDSO-G8")
      (fields (field (name "MANUFACTURER_PART_NUMBER") "TPS5450DDA"))
      (libsource (lib "eagle-import") (part "TPS5450DDAR"))
    )
  )
  (nets
    (net (code "1") (name "+5V") (class "Default")
      (node (ref "C23") (pin "A") (pinfunction "+_A") (pintype "passive"))
      (node (ref "R16") (pin "2") (pinfunction "2_2") (pintype "passive"))
      (node (ref "U3") (pin "3") (pinfunction "IN_3") (pintype "power_in"))
    )
    (net (code "2") (name "1,2EN") (class "Default")
      (node (ref "IC2") (pin "1") (pinfunction "1_1") (pintype "passive"))
    )
    (net (code "3") (name "1A") (class "Default")
      (node (ref "IC2") (pin "2") (pinfunction "2_2") (pintype "passive"))
    )
    (net (code "4") (name "1Y") (class "Default")
      (node (ref "IC2") (pin "3") (pinfunction "3_3") (pintype "passive"))
    )
    (net (code "5") (name "2A") (class "Default")
      (node (ref "IC2") (pin "7") (pinfunction "7_7") (pintype "passive"))
    )
    (net (code "6") (name "2Y") (class "Default")
      (node (ref "IC2") (pin "6") (pinfunction "6_6") (pintype "passive"))
    )
    (net (code "7") (name "3,4EN") (class "Default")
      (node (ref "IC2") (pin "9") (pinfunction "9_9") (pintype "passive"))
    )
    (net (code "8") (name "3.3V") (class "Default")
      (node (ref "C24") (pin "A") (pinfunction "+_A") (pintype "passive"))
      (node (ref "C25") (pin "1") (pinfunction "1_1") (pintype "passive"))
      (node (ref "C26") (pin "1") (pinfunction "1_1") (pintype "passive"))
      (node (ref "IC1") (pin "10") (pinfunction "RC2/AN11/C2IND/CTPLS/RP13_10") (pintype "bidirectional"))
      (node (ref "IC1") (pin "25") (pinfunction "RB7/CCP7/KBI3/PGD/RP10_25") (pintype "bidirectional"))
      (node (ref "IC3") (pin "10") (pinfunction "RC2/AN11/C2IND/CTPLS/RP13_10") (pintype "bidirectional"))
      (node (ref "IC3") (pin "25") (pinfunction "RB7/CCP7/KBI3/PGD/RP10_25") (pintype "bidirectional"))
      (node (ref "PROG.") (pin "2") (pinfunction "S_2") (pintype "passive"))
      (node (ref "R14") (pin "2") (pinfunction "2_2") (pintype "passive"))
      (node (ref "R15") (pin "1") (pinfunction "1_1") (pintype "passive"))
      (node (ref "U$6") (pin "P$1") (pinfunction "P1_P$1") (pintype "bidirectional"))
      (node (ref "U$6") (pin "P$4") (pinfunction "P4_P$4") (pintype "bidirectional"))
      (node (ref "U$7") (pin "P$1") (pinfunction "P1_P$1") (pintype "bidirectional"))
      (node (ref "U$7") (pin "P$4") (pinfunction "P4_P$4") (pintype "bidirectional"))
      (node (ref "U3") (pin "4") (pinfunction "VOUT_4") (pintype "power_in"))
    )
    (net (code "9") (name "3A") (class "Default")
      (node (ref "IC2") (pin "10") (pinfunction "10_10") (pintype "passive"))
    )
    (net (code "10") (name "3Y") (class "Default")
      (node (ref "IC2") (pin "11") (pinfunction "11_11") (pintype "passive"))
    )
    (net (code "11") (name "4A") (class "Default")
      (node (ref "IC2") (pin "15") (pinfunction "15_15") (pintype "passive"))
    )
    (net (code "12") (name "4Y") (class "Default")
      (node (ref "IC2") (pin "14") (pinfunction "14_14") (pintype "passive"))
    )
    (net (code "13") (name "BOOT_5") (class "Default")
      (node (ref "C17") (pin "1") (pinfunction "1_1") (pintype "passive"))
      (node (ref "C5") (pin "1") (pinfunction "1_1") (pintype "passive"))
      (node (ref "U$2") (pin "1") (pinfunction "BOOT_1") (pintype "passive"))
      (node (ref "U1") (pin "1") (pinfunction "BOOT_1") (pintype "passive"))
    )
    (net (code "14") (name "BOOT_MOTOR") (class "Default")
      (node (ref "C11") (pin "1") (pinfunction "1_1") (pintype "passive"))
      (node (ref "C20'") (pin "1") (pinfunction "1_1") (pintype "passive"))
      (node (ref "U$4") (pin "1") (pinfunction "BOOT_1") (pintype "passive"))
      (node (ref "U2") (pin "1") (pinfunction "BOOT_1") (pintype "passive"))
    )
    (net (code "15") (name "ENA_1") (class "Default")
      (node (ref "Q1") (pin "3") (pinfunction "D_3") (pintype "passive"))
      (node (ref "U1") (pin "5") (pinfunction "ENA_5") (pintype "passive"))
    )
    (net (code "16") (name "ENA_5") (class "Default")
      (node (ref "Q2") (pin "3") (pinfunction "D_3") (pintype "passive"))
      (node (ref "U$2") (pin "5") (pinfunction "ENA_5") (pintype "passive"))
    )
    (net (code "17") (name "ENA_MOTOR") (class "Default")
      (node (ref "Q3") (pin "3") (pinfunction "D_3") (pintype "passive"))
      (node (ref "Q4") (pin "3") (pinfunction "D_3") (pintype "passive"))
      (node (ref "U$4") (pin "5") (pinfunction "ENA_5") (pintype "passive"))
      (node (ref "U2") (pin "5") (pinfunction "ENA_5") (pintype "passive"))
    )
    (net (code "18") (name "GND") (class "Default")
      (node (ref "C1") (pin "1") (pinfunction "1_1") (pintype "passive"))
      (node (ref "C10") (pin "1") (pinfunction "1_1") (pintype "passive"))
      (node (ref "C12") (pin "2") (pinfunction "-_2") (pintype "passive"))
      (node (ref "C13") (pin "1") (pinfunction "1_1") (pintype "passive"))
      (node (ref "C14") (pin "1") (pinfunction "1_1") (pintype "passive"))
      (node (ref "C15") (pin "1") (pinfunction "1_1") (pintype "passive"))
      (node (ref "C16") (pin "1") (pinfunction "1_1") (pintype "passive"))
      (node (ref "C18") (pin "2") (pinfunction "-_2") (pintype "passive"))
      (node (ref "C19") (pin "1") (pinfunction "1_1") (pintype "passive"))
      (node (ref "C19'") (pin "1") (pinfunction "1_1") (pintype "passive"))
      (node (ref "C2") (pin "1") (pinfunction "1_1") (pintype "passive"))
      (node (ref "C20") (pin "1") (pinfunction "1_1") (pintype "passive"))
      (node (ref "C21") (pin "2") (pinfunction "2_2") (pintype "passive"))
      (node (ref "C21'") (pin "2") (pinfunction "-_2") (pintype "passive"))
      (node (ref "C22") (pin "1") (pinfunction "1_1") (pintype "passive"))
      (node (ref "C25") (pin "2") (pinfunction "2_2") (pintype "passive"))
      (node (ref "C26") (pin "2") (pinfunction "2_2") (pintype "passive"))
      (node (ref "C3") (pin "1") (pinfunction "1_1") (pintype "passive"))
      (node (ref "C4") (pin "1") (pinfunction "1_1") (pintype "passive"))
      (node (ref "C6") (pin "2") (pinfunction "-_2") (pintype "passive"))
      (node (ref "C7") (pin "1") (pinfunction "1_1") (pintype "passive"))
      (node (ref "C8") (pin "1") (pinfunction "1_1") (pintype "passive"))
      (node (ref "C9") (pin "1") (pinfunction "1_1") (pintype "passive"))
      (node (ref "D1") (pin "1") (pinfunction "A_2_1") (pintype "passive"))
      (node (ref "D2") (pin "1") (pinfunction "A_2_1") (pintype "passive"))
      (node (ref "D3") (pin "1") (pinfunction "A_2_1") (pintype "passive"))
      (node (ref "D4") (pin "1") (pinfunction "A_2_1") (pintype "passive"))
      (node (ref "IC1") (pin "24") (pinfunction "RB6/CCP6/KBI2/PGC/RP9_24") (pintype "bidirectional"))
      (node (ref "IC1") (pin "5") (pinfunction "VSS1_5") (pintype "input"))
      (node (ref "IC2") (pin "12") (pinfunction "12_12") (pintype "passive"))
      (node (ref "IC2") (pin "13") (pinfunction "13_13") (pintype "passive"))
      (node (ref "IC2") (pin "4") (pinfunction "4_4") (pintype "passive"))
      (node (ref "IC2") (pin "5") (pinfunction "5_5") (pintype "passive"))
      (node (ref "IC3") (pin "24") (pinfunction "RB6/CCP6/KBI2/PGC/RP9_24") (pintype "bidirectional"))
      (node (ref "IC3") (pin "5") (pinfunction "VSS1_5") (pintype "input"))
      (node (ref "J13") (pin "1") (pinfunction "S_1") (pintype "passive"))
      (node (ref "J13") (pin "4") (pinfunction "S_4") (pintype "passive"))
      (node (ref "LED1") (pin "C") (pinfunction "C_C") (pintype "passive"))
      (node (ref "LED2") (pin "C") (pinfunction "C_C") (pintype "passive"))
      (node (ref "LED3") (pin "C") (pinfunction "C_C") (pintype "passive"))
      (node (ref "LED4") (pin "C") (pinfunction "C_C") (pintype "passive"))
      (node (ref "LED5") (pin "C") (pinfunction "C_C") (pintype "passive"))
      (node (ref "LED6") (pin "C") (pinfunction "C_C") (pintype "passive"))
      (node (ref "LED7") (pin "C") (pinfunction "C_C") (pintype "passive"))
      (node (ref "LED8") (pin "C") (pinfunction "C_C") (pintype "passive"))
      (node (ref "LED9") (pin "C") (pinfunction "C_C") (pintype "passive"))
      (node (ref "PROG.") (pin "3") (pinfunction "S_3") (pintype "passive"))
      (node (ref "Q1") (pin "2") (pinfunction "S_2") (pintype "passive"))
      (node (ref "Q2") (pin "2") (pinfunction "S_2") (pintype "passive"))
      (node (ref "Q3") (pin "2") (pinfunction "S_2") (pintype "passive"))
      (node (ref "Q4") (pin "2") (pinfunction "S_2") (pintype "passive"))
      (node (ref "R11") (pin "1") (pinfunction "1_1") (pintype "passive"))
      (node (ref "R19") (pin "2") (pinfunction "2_2") (pintype "passive"))
      (node (ref "R20") (pin "2") (pinfunction "2_2") (pintype "passive"))
      (node (ref "R3") (pin "1") (pinfunction "1_1") (pintype "passive"))
      (node (ref "R5") (pin "1") (pinfunction "1_1") (pintype "passive"))
      (node (ref "R9") (pin "1") (pinfunction "1_1") (pintype "passive"))
      (node (ref "U$1") (pin "P8.1") (pinfunction "DGND_P8.1") (pintype "bidirectional"))
      (node (ref "U$1") (pin "P8.2") (pinfunction "DGND_P8.2") (pintype "bidirectional"))
      (node (ref "U$1") (pin "P9.1") (pinfunction "DGND_P9.1") (pintype "bidirectional"))
      (node (ref "U$1") (pin "P9.2") (pinfunction "DGND_P9.2") (pintype "bidirectional"))
      (node (ref "U$1") (pin "P9.43") (pinfunction "DGND_P9.43") (pintype "bidirectional"))
      (node (ref "U$1") (pin "P9.44") (pinfunction "DGND_P9.44") (pintype "bidirectional"))
      (node (ref "U$1") (pin "P9.45") (pinfunction "DGND_P9.45") (pintype "bidirectional"))
      (node (ref "U$1") (pin "P9.46") (pinfunction "DGND_P9.46") (pintype "bidirectional"))
      (node (ref "U$2") (pin "6") (pinfunction "GND_2_6") (pintype "passive"))
      (node (ref "U$2") (pin "9") (pinfunction "PWPD_9") (pintype "passive"))
      (node (ref "U$4") (pin "6") (pinfunction "GND_2_6") (pintype "passive"))
      (node (ref "U$4") (pin "9") (pinfunction "PWPD_9") (pintype "passive"))
      (node (ref "U$5") (pin "P$1") (pinfunction "P1_P$1") (pintype "bidirectional"))
      (node (ref "U$5") (pin "P$4") (pinfunction "P4_P$4") (pintype "bidirectional"))
      (node (ref "U1") (pin "6") (pinfunction "GND_2_6") (pintype "passive"))
      (node (ref "U1") (pin "9") (pinfunction "PWPD_9") (pintype "passive"))
      (node (ref "U2") (pin "6") (pinfunction "GND_2_6") (pintype "passive"))
      (node (ref "U2") (pin "9") (pinfunction "PWPD_9") (pintype "passive"))
    )
    (net (code "19") (name "IO3") (class "Default")
      (node (ref "IC3") (pin "7") (pinfunction "OSC2/CLKO/RA6_7") (pintype "bidirectional"))
      (node (ref "R21") (pin "2") (pinfunction "2_2") (pintype "passive"))
    )
    (net (code "20") (name "IO3(1)") (class "Default")
      (node (ref "IC1") (pin "7") (pinfunction "OSC2/CLKO/RA6_7") (pintype "bidirectional"))
    )
    (net (code "21") (name "IO4") (class "Default")
      (node (ref "IC1") (pin "9") (pinfunction "RC1/CCP8/T1OSI/~{UOE}/RP12_9") (pintype "bidirectional"))
      (node (ref "IC3") (pin "9") (pinfunction "RC1/CCP8/T1OSI/~{UOE}/RP12_9") (pintype "bidirectional"))
      (node (ref "R25") (pin "2") (pinfunction "2_2") (pintype "passive"))
    )
    (net (code "22") (name "IO5") (class "Default")
      (node (ref "IC3") (pin "11") (pinfunction "VUSB_11") (pintype "input"))
      (node (ref "R24") (pin "2") (pinfunction "2_2") (pintype "passive"))
    )
    (net (code "23") (name "IO5(1)") (class "Default")
      (node (ref "IC1") (pin "11") (pinfunction "VUSB_11") (pintype "input"))
    )
    (net (code "24") (name "IO6") (class "Default")
      (node (ref "IC1") (pin "12") (pinfunction "RC4/D-/VM_12") (pintype "bidirectional"))
      (node (ref "IC3") (pin "12") (pinfunction "RC4/D-/VM_12") (pintype "bidirectional"))
      (node (ref "R22") (pin "2") (pinfunction "2_2") (pintype "passive"))
    )
    (net (code "25") (name "IO7") (class "Default")
      (node (ref "IC3") (pin "13") (pinfunction "RC5/D+/VP_13") (pintype "bidirectional"))
      (node (ref "R23") (pin "2") (pinfunction "2_2") (pintype "passive"))
    )
    (net (code "26") (name "IO7(1)") (class "Default")
      (node (ref "IC1") (pin "13") (pinfunction "RC5/D+/VP_13") (pintype "bidirectional"))
    )
    (net (code "27") (name "IO8") (class "Default")
      (node (ref "IC3") (pin "28") (pinfunction "RA1/AN1/C2INA/VBG/RP1_28") (pintype "bidirectional"))
    )
    (net (code "28") (name "IO8(1)") (class "Default")
      (node (ref "IC1") (pin "28") (pinfunction "RA1/AN1/C2INA/VBG/RP1_28") (pintype "bidirectional"))
    )
    (net (code "29") (name "LVP") (class "Default")
      (node (ref "PROG.") (pin "6") (pinfunction "S_6") (pintype "passive"))
    )
    (net (code "30") (name "MCLR") (class "Default")
      (node (ref "C21") (pin "1") (pinfunction "1_1") (pintype "passive"))
      (node (ref "PROG.") (pin "1") (pinfunction "S_1") (pintype "passive"))
      (node (ref "R13") (pin "2") (pinfunction "2_2") (pintype "passive"))
      (node (ref "R14") (pin "1") (pinfunction "1_1") (pintype "passive"))
      (node (ref "U$5") (pin "P$2") (pinfunction "P2_P$2") (pintype "bidirectional"))
      (node (ref "U$5") (pin "P$3") (pinfunction "P3_P$3") (pintype "bidirectional"))
    )
    (net (code "31") (name "MCLR'") (class "Default")
      (node (ref "IC3") (pin "26") (pinfunction "~{MCLR}_26") (pintype "input"))
      (node (ref "R13") (pin "1") (pinfunction "1_1") (pintype "passive"))
    )
    (net (code "32") (name "MCLR'(1)") (class "Default")
      (node (ref "IC1") (pin "26") (pinfunction "~{MCLR}_26") (pintype "input"))
    )
    (net (code "33") (name "N$19") (class "Default")
      (node (ref "IC2") (pin "8") (pinfunction "8_8") (pintype "passive"))
    )
    (net (code "34") (name "N$20") (class "Default")
      (node (ref "IC2") (pin "16") (pinfunction "16_16") (pintype "passive"))
    )
    (net (code "35") (name "N$25") (class "Default")
      (node (ref "IC1") (pin "8") (pinfunction "RC0/T1OSO/T1CKI/RP11_8") (pintype "bidirectional"))
      (node (ref "IC3") (pin "8") (pinfunction "RC0/T1OSO/T1CKI/RP11_8") (pintype "bidirectional"))
    )
    (net (code "36") (name "N$31") (class "Default")
      (node (ref "IC1") (pin "14") (pinfunction "RC6/CCP9/TX1/CK1/RP17_14") (pintype "bidirectional"))
      (node (ref "IC3") (pin "14") (pinfunction "RC6/CCP9/TX1/CK1/RP17_14") (pintype "bidirectional"))
    )
    (net (code "37") (name "Net-(D5-PadA)") (class "Default")
      (node (ref "D5") (pin "A") (pinfunction "A_A") (pintype "passive"))
      (node (ref "R15") (pin "2") (pinfunction "2_2") (pintype "passive"))
    )
    (net (code "38") (name "Net-(D6-PadA)") (class "Default")
      (node (ref "D6") (pin "A") (pinfunction "A_A") (pintype "passive"))
      (node (ref "R16") (pin "1") (pinfunction "1_1") (pintype "passive"))
    )
    (net (code "39") (name "Net-(LED1-PadA)") (class "Default")
      (node (ref "LED1") (pin "A") (pinfunction "A_A") (pintype "passive"))
      (node (ref "R6") (pin "1") (pinfunction "1_1") (pintype "passive"))
    )
    (net (code "40") (name "Net-(LED2-PadA)") (class "Default")
      (node (ref "LED2") (pin "A") (pinfunction "A_A") (pintype "passive"))
      (node (ref "R10") (pin "1") (pinfunction "1_1") (pintype "passive"))
    )
    (net (code "41") (name "Net-(LED3-PadA)") (class "Default")
      (node (ref "LED3") (pin "A") (pinfunction "A_A") (pintype "passive"))
      (node (ref "R12") (pin "1") (pinfunction "1_1") (pintype "passive"))
    )
    (net (code "42") (name "Net-(LED4-PadA)") (class "Default")
      (node (ref "LED4") (pin "A") (pinfunction "A_A") (pintype "passive"))
      (node (ref "R4") (pin "1") (pinfunction "1_1") (pintype "passive"))
    )
    (net (code "43") (name "Net-(LED5-PadA)") (class "Default")
      (node (ref "LED5") (pin "A") (pinfunction "A_A") (pintype "passive"))
      (node (ref "R21") (pin "1") (pinfunction "1_1") (pintype "passive"))
    )
    (net (code "44") (name "Net-(LED6-PadA)") (class "Default")
      (node (ref "LED6") (pin "A") (pinfunction "A_A") (pintype "passive"))
      (node (ref "R22") (pin "1") (pinfunction "1_1") (pintype "passive"))
    )
    (net (code "45") (name "Net-(LED7-PadA)") (class "Default")
      (node (ref "LED7") (pin "A") (pinfunction "A_A") (pintype "passive"))
      (node (ref "R23") (pin "1") (pinfunction "1_1") (pintype "passive"))
    )
    (net (code "46") (name "Net-(LED8-PadA)") (class "Default")
      (node (ref "LED8") (pin "A") (pinfunction "A_A") (pintype "passive"))
      (node (ref "R24") (pin "1") (pinfunction "1_1") (pintype "passive"))
    )
    (net (code "47") (name "Net-(LED9-PadA)") (class "Default")
      (node (ref "LED9") (pin "A") (pinfunction "A_A") (pintype "passive"))
      (node (ref "R25") (pin "1") (pinfunction "1_1") (pintype "passive"))
    )
    (net (code "48") (name "Net-(U$2-VSNS)") (class "Default")
      (node (ref "R1") (pin "1") (pinfunction "1_1") (pintype "passive"))
      (node (ref "R5") (pin "2") (pinfunction "2_2") (pintype "passive"))
      (node (ref "U$2") (pin "4") (pinfunction "VSNS_4") (pintype "passive"))
    )
    (net (code "49") (name "Net-(U$4-VSNS)") (class "Default")
      (node (ref "R11") (pin "2") (pinfunction "2_2") (pintype "passive"))
      (node (ref "R7") (pin "1") (pinfunction "1_1") (pintype "passive"))
      (node (ref "U$4") (pin "4") (pinfunction "VSNS_4") (pintype "passive"))
    )
    (net (code "50") (name "Net-(U1-VSNS)") (class "Default")
      (node (ref "R2") (pin "1") (pinfunction "1_1") (pintype "passive"))
      (node (ref "R3") (pin "2") (pinfunction "2_2") (pintype "passive"))
      (node (ref "U1") (pin "4") (pinfunction "VSNS_4") (pintype "passive"))
    )
    (net (code "51") (name "Net-(U2-VSNS)") (class "Default")
      (node (ref "R8") (pin "1") (pinfunction "1_1") (pintype "passive"))
      (node (ref "R9") (pin "2") (pinfunction "2_2") (pintype "passive"))
      (node (ref "U2") (pin "4") (pinfunction "VSNS_4") (pintype "passive"))
    )
    (net (code "52") (name "OC1") (class "Default")
      (node (ref "IC1") (pin "23") (pinfunction "RB5/CCP5/KBI1/SDI1/SDA1/RP8_23") (pintype "bidirectional"))
      (node (ref "IC3") (pin "23") (pinfunction "RB5/CCP5/KBI1/SDI1/SDA1/RP8_23") (pintype "bidirectional"))
      (node (ref "J2") (pin "1") (pinfunction "S_1") (pintype "passive"))
    )
    (net (code "53") (name "OC2") (class "Default")
      (node (ref "IC1") (pin "22") (pinfunction "RB4/CCP4/KBI0/SCK1/SCL1/RP7_22") (pintype "bidirectional"))
      (node (ref "IC3") (pin "22") (pinfunction "RB4/CCP4/KBI0/SCK1/SCL1/RP7_22") (pintype "bidirectional"))
      (node (ref "J1") (pin "1") (pinfunction "S_1") (pintype "passive"))
    )
    (net (code "54") (name "OC3") (class "Default")
      (node (ref "IC1") (pin "21") (pinfunction "RB3/AN9/C3INA/CTED2/VPO/RP6_21") (pintype "bidirectional"))
      (node (ref "IC3") (pin "21") (pinfunction "RB3/AN9/C3INA/CTED2/VPO/RP6_21") (pintype "bidirectional"))
      (node (ref "J3") (pin "1") (pinfunction "S_1") (pintype "passive"))
    )
    (net (code "55") (name "OC4") (class "Default")
      (node (ref "IC3") (pin "19") (pinfunction "RB1/AN10/C3INC/RTCC/RP4_19") (pintype "bidirectional"))
      (node (ref "J4") (pin "1") (pinfunction "S_1") (pintype "passive"))
    )
    (net (code "56") (name "OC4(1)") (class "Default")
      (node (ref "IC1") (pin "19") (pinfunction "RB1/AN10/C3INC/RTCC/RP4_19") (pintype "bidirectional"))
    )
    (net (code "57") (name "OC5") (class "Default")
      (node (ref "IC3") (pin "18") (pinfunction "RB0/AN12/C3IND/INT0/RP3_18") (pintype "bidirectional"))
      (node (ref "J5") (pin "1") (pinfunction "S_1") (pintype "passive"))
    )
    (net (code "58") (name "OC5(1)") (class "Default")
      (node (ref "IC1") (pin "18") (pinfunction "RB0/AN12/C3IND/INT0/RP3_18") (pintype "bidirectional"))
    )
    (net (code "59") (name "OC6") (class "Default")
      (node (ref "IC3") (pin "15") (pinfunction "RC7/CCP10/RX1/DT1/SDO1/RP18_15") (pintype "bidirectional"))
      (node (ref "J6") (pin "1") (pinfunction "S_1") (pintype "passive"))
    )
    (net (code "60") (name "OC6(1)") (class "Default")
      (node (ref "IC1") (pin "15") (pinfunction "RC7/CCP10/RX1/DT1/SDO1/RP18_15") (pintype "bidirectional"))
    )
    (net (code "61") (name "PGC1") (class "Default")
      (node (ref "IC3") (pin "2") (pinfunction "RA3/AN3/C1INB/VREF+_2") (pintype "bidirectional"))
      (node (ref "PROG.") (pin "5") (pinfunction "S_5") (pintype "passive"))
    )
    (net (code "62") (name "PGC1(1)") (class "Default")
      (node (ref "IC1") (pin "2") (pinfunction "RA3/AN3/C1INB/VREF+_2") (pintype "bidirectional"))
    )
    (net (code "63") (name "PGD1") (class "Default")
      (node (ref "IC3") (pin "1") (pinfunction "RA2/AN2/C2INB/C1IND/C3INB/VREF-/CVREF_1") (pintype "bidirectional"))
      (node (ref "PROG.") (pin "4") (pinfunction "S_4") (pintype "passive"))
    )
    (net (code "64") (name "PGD1(1)") (class "Default")
      (node (ref "IC1") (pin "1") (pinfunction "RA2/AN2/C2INB/C1IND/C3INB/VREF-/CVREF_1") (pintype "bidirectional"))
    )
    (net (code "65") (name "PH_5") (class "Default")
      (node (ref "C17") (pin "2") (pinfunction "2_2") (pintype "passive"))
      (node (ref "C5") (pin "2") (pinfunction "2_2") (pintype "passive"))
      (node (ref "D1") (pin "3") (pinfunction "K_3") (pintype "passive"))
      (node (ref "D2") (pin "3") (pinfunction "K_3") (pintype "passive"))
      (node (ref "L1") (pin "1") (pinfunction "1_1") (pintype "passive"))
      (node (ref "L2") (pin "1") (pinfunction "1_1") (pintype "passive"))
      (node (ref "U$2") (pin "8") (pinfunction "PH_8") (pintype "passive"))
      (node (ref "U1") (pin "8") (pinfunction "PH_8") (pintype "passive"))
    )
    (net (code "66") (name "PH_MOTOR") (class "Default")
      (node (ref "C11") (pin "2") (pinfunction "2_2") (pintype "passive"))
      (node (ref "C20'") (pin "2") (pinfunction "2_2") (pintype "passive"))
      (node (ref "D3") (pin "3") (pinfunction "K_3") (pintype "passive"))
      (node (ref "D4") (pin "3") (pinfunction "K_3") (pintype "passive"))
      (node (ref "L3") (pin "1") (pinfunction "1_1") (pintype "passive"))
      (node (ref "L4") (pin "1") (pinfunction "1_1") (pintype "passive"))
      (node (ref "U$4") (pin "8") (pinfunction "PH_8") (pintype "passive"))
      (node (ref "U2") (pin "8") (pinfunction "PH_8") (pintype "passive"))
    )
    (net (code "67") (name "POWER_EN(1)") (class "Default")
      (node (ref "Q1") (pin "1") (pinfunction "G_1") (pintype "passive"))
    )
    (net (code "68") (name "POWER_EN(2)") (class "Default")
      (node (ref "Q3") (pin "1") (pinfunction "G_1") (pintype "passive"))
    )
    (net (code "69") (name "POWER_EN(3)") (class "Default")
      (node (ref "Q2") (pin "1") (pinfunction "G_1") (pintype "passive"))
    )
    (net (code "70") (name "POWER_EN(4)") (class "Default")
      (node (ref "Q4") (pin "1") (pinfunction "G_1") (pintype "passive"))
    )
    (net (code "71") (name "SCL") (class "Default")
      (node (ref "IC1") (pin "4") (pinfunction "RA5/AN4/C1INC/~{SS1}/HLVDIN/RCV/RP2_4") (pintype "bidirectional"))
      (node (ref "IC3") (pin "4") (pinfunction "RA5/AN4/C1INC/~{SS1}/HLVDIN/RCV/RP2_4") (pintype "bidirectional"))
      (node (ref "U$1") (pin "P9.19") (pinfunction "I2C2_SCL_P9.19") (pintype "bidirectional"))
    )
    (net (code "72") (name "SDA") (class "Default")
      (node (ref "IC1") (pin "3") (pinfunction "VDDCORE/VCAP_3") (pintype "input"))
      (node (ref "IC3") (pin "3") (pinfunction "VDDCORE/VCAP_3") (pintype "input"))
      (node (ref "U$1") (pin "P9.20") (pinfunction "I2C2_SDA_P9.20") (pintype "bidirectional"))
    )
    (net (code "73") (name "SWITCH_1") (class "Default")
      (node (ref "IC3") (pin "27") (pinfunction "RA0/AN0/C1INA/ULPWU/RP0_27") (pintype "bidirectional"))
      (node (ref "R19") (pin "1") (pinfunction "1_1") (pintype "passive"))
      (node (ref "U$6") (pin "P$2") (pinfunction "P2_P$2") (pintype "bidirectional"))
      (node (ref "U$6") (pin "P$3") (pinfunction "P3_P$3") (pintype "bidirectional"))
    )
    (net (code "74") (name "SWITCH_2") (class "Default")
      (node (ref "IC3") (pin "6") (pinfunction "OSC1/CLKI/RA7_6") (pintype "bidirectional"))
      (node (ref "R20") (pin "1") (pinfunction "1_1") (pintype "passive"))
      (node (ref "U$7") (pin "P$2") (pinfunction "P2_P$2") (pintype "bidirectional"))
      (node (ref "U$7") (pin "P$3") (pinfunction "P3_P$3") (pintype "bidirectional"))
    )
    (net (code "75") (name "VCC") (class "Default")
      (node (ref "C1") (pin "2") (pinfunction "2_2") (pintype "passive"))
      (node (ref "C10") (pin "2") (pinfunction "2_2") (pintype "passive"))
      (node (ref "C13") (pin "2") (pinfunction "2_2") (pintype "passive"))
      (node (ref "C14") (pin "2") (pinfunction "2_2") (pintype "passive"))
      (node (ref "C15") (pin "2") (pinfunction "2_2") (pintype "passive"))
      (node (ref "C16") (pin "2") (pinfunction "2_2") (pintype "passive"))
      (node (ref "C19") (pin "2") (pinfunction "2_2") (pintype "passive"))
      (node (ref "C19'") (pin "2") (pinfunction "2_2") (pintype "passive"))
      (node (ref "C2") (pin "2") (pinfunction "2_2") (pintype "passive"))
      (node (ref "C20") (pin "2") (pinfunction "2_2") (pintype "passive"))
      (node (ref "C22") (pin "2") (pinfunction "2_2") (pintype "passive"))
      (node (ref "C3") (pin "2") (pinfunction "2_2") (pintype "passive"))
      (node (ref "C4") (pin "2") (pinfunction "2_2") (pintype "passive"))
      (node (ref "C7") (pin "2") (pinfunction "2_2") (pintype "passive"))
      (node (ref "C8") (pin "2") (pinfunction "2_2") (pintype "passive"))
      (node (ref "C9") (pin "2") (pinfunction "2_2") (pintype "passive"))
      (node (ref "U$2") (pin "7") (pinfunction "VIN_7") (pintype "passive"))
      (node (ref "U$4") (pin "7") (pinfunction "VIN_7") (pintype "passive"))
      (node (ref "U1") (pin "7") (pinfunction "VIN_7") (pintype "passive"))
      (node (ref "U2") (pin "7") (pinfunction "VIN_7") (pintype "passive"))
    )
    (net (code "76") (name "VOUT_LOGIC") (class "Default")
      (node (ref "C12") (pin "1") (pinfunction "+_1") (pintype "passive"))
      (node (ref "L3") (pin "2") (pinfunction "2_2") (pintype "passive"))
      (node (ref "R10") (pin "2") (pinfunction "2_2") (pintype "passive"))
      (node (ref "R8") (pin "2") (pinfunction "2_2") (pintype "passive"))
    )
    (net (code "77") (name "VOUT_MOTOR") (class "Default")
      (node (ref "C18") (pin "1") (pinfunction "+_1") (pintype "passive"))
      (node (ref "J13") (pin "2") (pinfunction "S_2") (pintype "passive"))
      (node (ref "J13") (pin "3") (pinfunction "S_3") (pintype "passive"))
      (node (ref "L2") (pin "2") (pinfunction "2_2") (pintype "passive"))
      (node (ref "R1") (pin "2") (pinfunction "2_2") (pintype "passive"))
      (node (ref "R6") (pin "2") (pinfunction "2_2") (pintype "passive"))
    )
    (net (code "78") (name "VOUT_SERVOLEFT") (class "Default")
      (node (ref "C28") (pin "1") (pinfunction "1_1") (pintype "passive"))
      (node (ref "C6") (pin "1") (pinfunction "+_1") (pintype "passive"))
      (node (ref "J4") (pin "2") (pinfunction "S_2") (pintype "passive"))
      (node (ref "J5") (pin "2") (pinfunction "S_2") (pintype "passive"))
      (node (ref "J6") (pin "2") (pinfunction "S_2") (pintype "passive"))
      (node (ref "L1") (pin "2") (pinfunction "2_2") (pintype "passive"))
      (node (ref "R2") (pin "2") (pinfunction "2_2") (pintype "passive"))
      (node (ref "R4") (pin "2") (pinfunction "2_2") (pintype "passive"))
    )
    (net (code "79") (name "VOUT_SERVORIGHT") (class "Default")
      (node (ref "C21'") (pin "1") (pinfunction "+_1") (pintype "passive"))
      (node (ref "C27") (pin "1") (pinfunction "1_1") (pintype "passive"))
      (node (ref "J1") (pin "2") (pinfunction "S_2") (pintype "passive"))
      (node (ref "J2") (pin "2") (pinfunction "S_2") (pintype "passive"))
      (node (ref "J3") (pin "2") (pinfunction "S_2") (pintype "passive"))
      (node (ref "L4") (pin "2") (pinfunction "2_2") (pintype "passive"))
      (node (ref "R12") (pin "2") (pinfunction "2_2") (pintype "passive"))
      (node (ref "R7") (pin "2") (pinfunction "2_2") (pintype "passive"))
    )
    (net (code "80") (name "VSS") (class "Default")
      (node (ref "C23") (pin "C") (pinfunction "-_C") (pintype "passive"))
      (node (ref "C24") (pin "C") (pinfunction "-_C") (pintype "passive"))
      (node (ref "C27") (pin "2") (pinfunction "2_2") (pintype "passive"))
      (node (ref "C28") (pin "2") (pinfunction "2_2") (pintype "passive"))
      (node (ref "D5") (pin "C") (pinfunction "C_C") (pintype "passive"))
      (node (ref "D6") (pin "C") (pinfunction "C_C") (pintype "passive"))
      (node (ref "J1") (pin "3") (pinfunction "S_3") (pintype "passive"))
      (node (ref "J2") (pin "3") (pinfunction "S_3") (pintype "passive"))
      (node (ref "J3") (pin "3") (pinfunction "S_3") (pintype "passive"))
      (node (ref "J4") (pin "3") (pinfunction "S_3") (pintype "passive"))
      (node (ref "J5") (pin "3") (pinfunction "S_3") (pintype "passive"))
      (node (ref "J6") (pin "3") (pinfunction "S_3") (pintype "passive"))
      (node (ref "U3") (pin "1") (pinfunction "GND_1") (pintype "passive"))
    )
    (net (code "81") (name "unconnected-(IC1-OSC1{slash}CLKI{slash}RA7-Pad6)") (class "Default")
      (node (ref "IC1") (pin "6") (pinfunction "OSC1/CLKI/RA7_6") (pintype "bidirectional"))
    )
    (net (code "82") (name "unconnected-(IC1-RA0{slash}AN0{slash}C1INA{slash}ULPWU{slash}RP0-Pad27)") (class "Default")
      (node (ref "IC1") (pin "27") (pinfunction "RA0/AN0/C1INA/ULPWU/RP0_27") (pintype "bidirectional"))
    )
    (net (code "83") (name "unconnected-(IC1-RB2{slash}AN8{slash}C2INC{slash}CTED1{slash}VMO{slash}REFO{slash}RP5-Pad20)") (class "Default")
      (node (ref "IC1") (pin "20") (pinfunction "RB2/AN8/C2INC/CTED1/VMO/REFO/RP5_20") (pintype "bidirectional"))
    )
    (net (code "84") (name "unconnected-(IC1-VDD-Pad17)") (class "Default")
      (node (ref "IC1") (pin "17") (pinfunction "VDD_17") (pintype "input"))
    )
    (net (code "85") (name "unconnected-(IC1-VSS2-Pad16)") (class "Default")
      (node (ref "IC1") (pin "16") (pinfunction "VSS2_16") (pintype "input"))
    )
    (net (code "86") (name "unconnected-(IC3-RB2{slash}AN8{slash}C2INC{slash}CTED1{slash}VMO{slash}REFO{slash}RP5-Pad20)") (class "Default")
      (node (ref "IC3") (pin "20") (pinfunction "RB2/AN8/C2INC/CTED1/VMO/REFO/RP5_20") (pintype "bidirectional"))
    )
    (net (code "87") (name "unconnected-(IC3-VDD-Pad17)") (class "Default")
      (node (ref "IC3") (pin "17") (pinfunction "VDD_17") (pintype "input"))
    )
    (net (code "88") (name "unconnected-(IC3-VSS2-Pad16)") (class "Default")
      (node (ref "IC3") (pin "16") (pinfunction "VSS2_16") (pintype "input"))
    )
    (net (code "89") (name "unconnected-(J7A-S-Pad1)") (class "Default")
      (node (ref "J7") (pin "1") (pinfunction "S_1") (pintype "passive"))
    )
    (net (code "90") (name "unconnected-(J7B-S-Pad2)") (class "Default")
      (node (ref "J7") (pin "2") (pinfunction "S_2") (pintype "passive"))
    )
    (net (code "91") (name "unconnected-(J8A-S-Pad1)") (class "Default")
      (node (ref "J8") (pin "1") (pinfunction "S_1") (pintype "passive"))
    )
    (net (code "92") (name "unconnected-(J8B-S-Pad2)") (class "Default")
      (node (ref "J8") (pin "2") (pinfunction "S_2") (pintype "passive"))
    )
    (net (code "93") (name "unconnected-(J9A-S-Pad1)") (class "Default")
      (node (ref "J9") (pin "1") (pinfunction "S_1") (pintype "passive"))
    )
    (net (code "94") (name "unconnected-(J9B-S-Pad2)") (class "Default")
      (node (ref "J9") (pin "2") (pinfunction "S_2") (pintype "passive"))
    )
    (net (code "95") (name "unconnected-(J10A-S-Pad1)") (class "Default")
      (node (ref "J10") (pin "1") (pinfunction "S_1") (pintype "passive"))
    )
    (net (code "96") (name "unconnected-(J10B-S-Pad2)") (class "Default")
      (node (ref "J10") (pin "2") (pinfunction "S_2") (pintype "passive"))
    )
    (net (code "97") (name "unconnected-(J11A-S-Pad1)") (class "Default")
      (node (ref "J11") (pin "1") (pinfunction "S_1") (pintype "passive"))
    )
    (net (code "98") (name "unconnected-(J11B-S-Pad2)") (class "Default")
      (node (ref "J11") (pin "2") (pinfunction "S_2") (pintype "passive"))
    )
    (net (code "99") (name "unconnected-(J12A-S-Pad1)") (class "Default")
      (node (ref "J12") (pin "1") (pinfunction "S_1") (pintype "passive"))
    )
    (net (code "100") (name "unconnected-(J12B-S-Pad2)") (class "Default")
      (node (ref "J12") (pin "2") (pinfunction "S_2") (pintype "passive"))
    )
    (net (code "101") (name "unconnected-(U$1A-GPIO_8-PadP8.35)") (class "Default")
      (node (ref "U$1") (pin "P8.35") (pinfunction "GPIO_8_P8.35") (pintype "bidirectional"))
    )
    (net (code "102") (name "unconnected-(U$1A-GPIO_9-PadP8.33)") (class "Default")
      (node (ref "U$1") (pin "P8.33") (pinfunction "GPIO_9_P8.33") (pintype "bidirectional"))
    )
    (net (code "103") (name "unconnected-(U$1A-GPIO_10-PadP8.31)") (class "Default")
      (node (ref "U$1") (pin "P8.31") (pinfunction "GPIO_10_P8.31") (pintype "bidirectional"))
    )
    (net (code "104") (name "unconnected-(U$1A-GPIO_11-PadP8.32)") (class "Default")
      (node (ref "U$1") (pin "P8.32") (pinfunction "GPIO_11_P8.32") (pintype "bidirectional"))
    )
    (net (code "105") (name "unconnected-(U$1A-GPIO_22-PadP8.19)") (class "Default")
      (node (ref "U$1") (pin "P8.19") (pinfunction "GPIO_22_P8.19") (pintype "bidirectional"))
    )
    (net (code "106") (name "unconnected-(U$1A-GPIO_23-PadP8.13)") (class "Default")
      (node (ref "U$1") (pin "P8.13") (pinfunction "GPIO_23_P8.13") (pintype "bidirectional"))
    )
    (net (code "107") (name "unconnected-(U$1A-GPIO_26-PadP8.14)") (class "Default")
      (node (ref "U$1") (pin "P8.14") (pinfunction "GPIO_26_P8.14") (pintype "bidirectional"))
    )
    (net (code "108") (name "unconnected-(U$1A-GPIO_27-PadP8.17)") (class "Default")
      (node (ref "U$1") (pin "P8.17") (pinfunction "GPIO_27_P8.17") (pintype "bidirectional"))
    )
    (net (code "109") (name "unconnected-(U$1A-GPIO_32-PadP8.25)") (class "Default")
      (node (ref "U$1") (pin "P8.25") (pinfunction "GPIO_32_P8.25") (pintype "bidirectional"))
    )
    (net (code "110") (name "unconnected-(U$1A-GPIO_33-PadP8.24)") (class "Default")
      (node (ref "U$1") (pin "P8.24") (pinfunction "GPIO_33_P8.24") (pintype "bidirectional"))
    )
    (net (code "111") (name "unconnected-(U$1A-GPIO_34-PadP8.5)") (class "Default")
      (node (ref "U$1") (pin "P8.5") (pinfunction "GPIO_34_P8.5") (pintype "bidirectional"))
    )
    (net (code "112") (name "unconnected-(U$1A-GPIO_35-PadP8.6)") (class "Default")
      (node (ref "U$1") (pin "P8.6") (pinfunction "GPIO_35_P8.6") (pintype "bidirectional"))
    )
    (net (code "113") (name "unconnected-(U$1A-GPIO_36-PadP8.23)") (class "Default")
      (node (ref "U$1") (pin "P8.23") (pinfunction "GPIO_36_P8.23") (pintype "bidirectional"))
    )
    (net (code "114") (name "unconnected-(U$1A-GPIO_37-PadP8.22)") (class "Default")
      (node (ref "U$1") (pin "P8.22") (pinfunction "GPIO_37_P8.22") (pintype "bidirectional"))
    )
    (net (code "115") (name "unconnected-(U$1A-GPIO_38-PadP8.3)") (class "Default")
      (node (ref "U$1") (pin "P8.3") (pinfunction "GPIO_38_P8.3") (pintype "bidirectional"))
    )
    (net (code "116") (name "unconnected-(U$1A-GPIO_39-PadP8.4)") (class "Default")
      (node (ref "U$1") (pin "P8.4") (pinfunction "GPIO_39_P8.4") (pintype "bidirectional"))
    )
    (net (code "117") (name "unconnected-(U$1A-GPIO_44-PadP8.12)") (class "Default")
      (node (ref "U$1") (pin "P8.12") (pinfunction "GPIO_44_P8.12") (pintype "bidirectional"))
    )
    (net (code "118") (name "unconnected-(U$1A-GPIO_45-PadP8.11)") (class "Default")
      (node (ref "U$1") (pin "P8.11") (pinfunction "GPIO_45_P8.11") (pintype "bidirectional"))
    )
    (net (code "119") (name "unconnected-(U$1A-GPIO_46-PadP8.16)") (class "Default")
      (node (ref "U$1") (pin "P8.16") (pinfunction "GPIO_46_P8.16") (pintype "bidirectional"))
    )
    (net (code "120") (name "unconnected-(U$1A-GPIO_47-PadP8.15)") (class "Default")
      (node (ref "U$1") (pin "P8.15") (pinfunction "GPIO_47_P8.15") (pintype "bidirectional"))
    )
    (net (code "121") (name "unconnected-(U$1A-GPIO_61-PadP8.26)") (class "Default")
      (node (ref "U$1") (pin "P8.26") (pinfunction "GPIO_61_P8.26") (pintype "bidirectional"))
    )
    (net (code "122") (name "unconnected-(U$1A-GPIO_62-PadP8.21)") (class "Default")
      (node (ref "U$1") (pin "P8.21") (pinfunction "GPIO_62_P8.21") (pintype "bidirectional"))
    )
    (net (code "123") (name "unconnected-(U$1A-GPIO_63-PadP8.20)") (class "Default")
      (node (ref "U$1") (pin "P8.20") (pinfunction "GPIO_63_P8.20") (pintype "bidirectional"))
    )
    (net (code "124") (name "unconnected-(U$1A-GPIO_65-PadP8.18)") (class "Default")
      (node (ref "U$1") (pin "P8.18") (pinfunction "GPIO_65_P8.18") (pintype "bidirectional"))
    )
    (net (code "125") (name "unconnected-(U$1A-GPIO_66-PadP8.7)") (class "Default")
      (node (ref "U$1") (pin "P8.7") (pinfunction "GPIO_66_P8.7") (pintype "bidirectional"))
    )
    (net (code "126") (name "unconnected-(U$1A-GPIO_67-PadP8.8)") (class "Default")
      (node (ref "U$1") (pin "P8.8") (pinfunction "GPIO_67_P8.8") (pintype "bidirectional"))
    )
    (net (code "127") (name "unconnected-(U$1A-GPIO_68-PadP8.10)") (class "Default")
      (node (ref "U$1") (pin "P8.10") (pinfunction "GPIO_68_P8.10") (pintype "bidirectional"))
    )
    (net (code "128") (name "unconnected-(U$1A-GPIO_69-PadP8.9)") (class "Default")
      (node (ref "U$1") (pin "P8.9") (pinfunction "GPIO_69_P8.9") (pintype "bidirectional"))
    )
    (net (code "129") (name "unconnected-(U$1A-GPIO_70-PadP8.45)") (class "Default")
      (node (ref "U$1") (pin "P8.45") (pinfunction "GPIO_70_P8.45") (pintype "bidirectional"))
    )
    (net (code "130") (name "unconnected-(U$1A-GPIO_71-PadP8.46)") (class "Default")
      (node (ref "U$1") (pin "P8.46") (pinfunction "GPIO_71_P8.46") (pintype "bidirectional"))
    )
    (net (code "131") (name "unconnected-(U$1A-GPIO_72-PadP8.43)") (class "Default")
      (node (ref "U$1") (pin "P8.43") (pinfunction "GPIO_72_P8.43") (pintype "bidirectional"))
    )
    (net (code "132") (name "unconnected-(U$1A-GPIO_73-PadP8.44)") (class "Default")
      (node (ref "U$1") (pin "P8.44") (pinfunction "GPIO_73_P8.44") (pintype "bidirectional"))
    )
    (net (code "133") (name "unconnected-(U$1A-GPIO_74-PadP8.41)") (class "Default")
      (node (ref "U$1") (pin "P8.41") (pinfunction "GPIO_74_P8.41") (pintype "bidirectional"))
    )
    (net (code "134") (name "unconnected-(U$1A-GPIO_75-PadP8.42)") (class "Default")
      (node (ref "U$1") (pin "P8.42") (pinfunction "GPIO_75_P8.42") (pintype "bidirectional"))
    )
    (net (code "135") (name "unconnected-(U$1A-GPIO_76-PadP8.39)") (class "Default")
      (node (ref "U$1") (pin "P8.39") (pinfunction "GPIO_76_P8.39") (pintype "bidirectional"))
    )
    (net (code "136") (name "unconnected-(U$1A-GPIO_77-PadP8.40)") (class "Default")
      (node (ref "U$1") (pin "P8.40") (pinfunction "GPIO_77_P8.40") (pintype "bidirectional"))
    )
    (net (code "137") (name "unconnected-(U$1A-GPIO_78-PadP8.37)") (class "Default")
      (node (ref "U$1") (pin "P8.37") (pinfunction "GPIO_78_P8.37") (pintype "bidirectional"))
    )
    (net (code "138") (name "unconnected-(U$1A-GPIO_79-PadP8.38)") (class "Default")
      (node (ref "U$1") (pin "P8.38") (pinfunction "GPIO_79_P8.38") (pintype "bidirectional"))
    )
    (net (code "139") (name "unconnected-(U$1A-GPIO_80-PadP8.36)") (class "Default")
      (node (ref "U$1") (pin "P8.36") (pinfunction "GPIO_80_P8.36") (pintype "bidirectional"))
    )
    (net (code "140") (name "unconnected-(U$1A-GPIO_81-PadP8.34)") (class "Default")
      (node (ref "U$1") (pin "P8.34") (pinfunction "GPIO_81_P8.34") (pintype "bidirectional"))
    )
    (net (code "141") (name "unconnected-(U$1A-GPIO_86-PadP8.27)") (class "Default")
      (node (ref "U$1") (pin "P8.27") (pinfunction "GPIO_86_P8.27") (pintype "bidirectional"))
    )
    (net (code "142") (name "unconnected-(U$1A-GPIO_87-PadP8.29)") (class "Default")
      (node (ref "U$1") (pin "P8.29") (pinfunction "GPIO_87_P8.29") (pintype "bidirectional"))
    )
    (net (code "143") (name "unconnected-(U$1A-GPIO_88-PadP8.28)") (class "Default")
      (node (ref "U$1") (pin "P8.28") (pinfunction "GPIO_88_P8.28") (pintype "bidirectional"))
    )
    (net (code "144") (name "unconnected-(U$1A-GPIO_89-PadP8.30)") (class "Default")
      (node (ref "U$1") (pin "P8.30") (pinfunction "GPIO_89_P8.30") (pintype "bidirectional"))
    )
    (net (code "145") (name "unconnected-(U$1B-AIN0-PadP9.39)") (class "Default")
      (node (ref "U$1") (pin "P9.39") (pinfunction "AIN0_P9.39") (pintype "bidirectional"))
    )
    (net (code "146") (name "unconnected-(U$1B-AIN1-PadP9.40)") (class "Default")
      (node (ref "U$1") (pin "P9.40") (pinfunction "AIN1_P9.40") (pintype "bidirectional"))
    )
    (net (code "147") (name "unconnected-(U$1B-AIN2-PadP9.37)") (class "Default")
      (node (ref "U$1") (pin "P9.37") (pinfunction "AIN2_P9.37") (pintype "bidirectional"))
    )
    (net (code "148") (name "unconnected-(U$1B-AIN3-PadP9.38)") (class "Default")
      (node (ref "U$1") (pin "P9.38") (pinfunction "AIN3_P9.38") (pintype "bidirectional"))
    )
    (net (code "149") (name "unconnected-(U$1B-AIN4-PadP9.33)") (class "Default")
      (node (ref "U$1") (pin "P9.33") (pinfunction "AIN4_P9.33") (pintype "bidirectional"))
    )
    (net (code "150") (name "unconnected-(U$1B-AIN5-PadP9.36)") (class "Default")
      (node (ref "U$1") (pin "P9.36") (pinfunction "AIN5_P9.36") (pintype "bidirectional"))
    )
    (net (code "151") (name "unconnected-(U$1B-AIN6-PadP9.35)") (class "Default")
      (node (ref "U$1") (pin "P9.35") (pinfunction "AIN6_P9.35") (pintype "bidirectional"))
    )
    (net (code "152") (name "unconnected-(U$1B-GNDA_ADC-PadP9.34)") (class "Default")
      (node (ref "U$1") (pin "P9.34") (pinfunction "GNDA_ADC_P9.34") (pintype "bidirectional"))
    )
    (net (code "153") (name "unconnected-(U$1B-GPIO_2-PadP9.22)") (class "Default")
      (node (ref "U$1") (pin "P9.22") (pinfunction "GPIO_2_P9.22") (pintype "bidirectional"))
    )
    (net (code "154") (name "unconnected-(U$1B-GPIO_3-PadP9.21)") (class "Default")
      (node (ref "U$1") (pin "P9.21") (pinfunction "GPIO_3_P9.21") (pintype "bidirectional"))
    )
    (net (code "155") (name "unconnected-(U$1B-GPIO_4-PadP9.17)") (class "Default")
      (node (ref "U$1") (pin "P9.17") (pinfunction "GPIO_4_P9.17") (pintype "bidirectional"))
    )
    (net (code "156") (name "unconnected-(U$1B-GPIO_5-PadP9.18)") (class "Default")
      (node (ref "U$1") (pin "P9.18") (pinfunction "GPIO_5_P9.18") (pintype "bidirectional"))
    )
    (net (code "157") (name "unconnected-(U$1B-GPIO_7-PadP9.42)") (class "Default")
      (node (ref "U$1") (pin "P9.42") (pinfunction "GPIO_7_P9.42") (pintype "bidirectional"))
    )
    (net (code "158") (name "unconnected-(U$1B-GPIO_14-PadP9.26)") (class "Default")
      (node (ref "U$1") (pin "P9.26") (pinfunction "GPIO_14_P9.26") (pintype "bidirectional"))
    )
    (net (code "159") (name "unconnected-(U$1B-GPIO_15-PadP9.24)") (class "Default")
      (node (ref "U$1") (pin "P9.24") (pinfunction "GPIO_15_P9.24") (pintype "bidirectional"))
    )
    (net (code "160") (name "unconnected-(U$1B-GPIO_20-PadP9.41)") (class "Default")
      (node (ref "U$1") (pin "P9.41") (pinfunction "GPIO_20_P9.41") (pintype "bidirectional"))
    )
    (net (code "161") (name "unconnected-(U$1B-GPIO_30-PadP9.11)") (class "Default")
      (node (ref "U$1") (pin "P9.11") (pinfunction "GPIO_30_P9.11") (pintype "bidirectional"))
    )
    (net (code "162") (name "unconnected-(U$1B-GPIO_31-PadP9.13)") (class "Default")
      (node (ref "U$1") (pin "P9.13") (pinfunction "GPIO_31_P9.13") (pintype "bidirectional"))
    )
    (net (code "163") (name "unconnected-(U$1B-GPIO_40-PadP9.14)") (class "Default")
      (node (ref "U$1") (pin "P9.14") (pinfunction "GPIO_40_P9.14") (pintype "bidirectional"))
    )
    (net (code "164") (name "unconnected-(U$1B-GPIO_48-PadP9.15)") (class "Default")
      (node (ref "U$1") (pin "P9.15") (pinfunction "GPIO_48_P9.15") (pintype "bidirectional"))
    )
    (net (code "165") (name "unconnected-(U$1B-GPIO_49-PadP9.23)") (class "Default")
      (node (ref "U$1") (pin "P9.23") (pinfunction "GPIO_49_P9.23") (pintype "bidirectional"))
    )
    (net (code "166") (name "unconnected-(U$1B-GPIO_51-PadP9.16)") (class "Default")
      (node (ref "U$1") (pin "P9.16") (pinfunction "GPIO_51_P9.16") (pintype "bidirectional"))
    )
    (net (code "167") (name "unconnected-(U$1B-GPIO_60-PadP9.12)") (class "Default")
      (node (ref "U$1") (pin "P9.12") (pinfunction "GPIO_60_P9.12") (pintype "bidirectional"))
    )
    (net (code "168") (name "unconnected-(U$1B-GPIO_117-PadP9.25)") (class "Default")
      (node (ref "U$1") (pin "P9.25") (pinfunction "GPIO_117_P9.25") (pintype "bidirectional"))
    )
    (net (code "169") (name "unconnected-(U$1B-GPIO_120-PadP9.31)") (class "Default")
      (node (ref "U$1") (pin "P9.31") (pinfunction "GPIO_120_P9.31") (pintype "bidirectional"))
    )
    (net (code "170") (name "unconnected-(U$1B-GPIO_121-PadP9.29)") (class "Default")
      (node (ref "U$1") (pin "P9.29") (pinfunction "GPIO_121_P9.29") (pintype "bidirectional"))
    )
    (net (code "171") (name "unconnected-(U$1B-GPIO_122-PadP9.30)") (class "Default")
      (node (ref "U$1") (pin "P9.30") (pinfunction "GPIO_122_P9.30") (pintype "bidirectional"))
    )
    (net (code "172") (name "unconnected-(U$1B-GPIO_123-PadP9.28)") (class "Default")
      (node (ref "U$1") (pin "P9.28") (pinfunction "GPIO_123_P9.28") (pintype "bidirectional"))
    )
    (net (code "173") (name "unconnected-(U$1B-GPIO_125-PadP9.27)") (class "Default")
      (node (ref "U$1") (pin "P9.27") (pinfunction "GPIO_125_P9.27") (pintype "bidirectional"))
    )
    (net (code "174") (name "unconnected-(U$1B-PWR_BUT-PadP9.9)") (class "Default")
      (node (ref "U$1") (pin "P9.9") (pinfunction "PWR_BUT_P9.9") (pintype "bidirectional"))
    )
    (net (code "175") (name "unconnected-(U$1B-SYS_5V-PadP9.7)") (class "Default")
      (node (ref "U$1") (pin "P9.7") (pinfunction "SYS_5V_P9.7") (pintype "bidirectional"))
    )
    (net (code "176") (name "unconnected-(U$1B-SYS_5V-PadP9.8)") (class "Default")
      (node (ref "U$1") (pin "P9.8") (pinfunction "SYS_5V_P9.8") (pintype "bidirectional"))
    )
    (net (code "177") (name "unconnected-(U$1B-SYS_RESET~{N}-PadP9.10)") (class "Default")
      (node (ref "U$1") (pin "P9.10") (pinfunction "SYS_RESET~{N}_P9.10") (pintype "bidirectional"))
    )
    (net (code "178") (name "unconnected-(U$1B-VDD_3V3-PadP9.3)") (class "Default")
      (node (ref "U$1") (pin "P9.3") (pinfunction "VDD_3V3_P9.3") (pintype "bidirectional"))
    )
    (net (code "179") (name "unconnected-(U$1B-VDD_3V3-PadP9.4)") (class "Default")
      (node (ref "U$1") (pin "P9.4") (pinfunction "VDD_3V3_P9.4") (pintype "bidirectional"))
    )
    (net (code "180") (name "unconnected-(U$1B-VDD_5V-PadP9.5)") (class "Default")
      (node (ref "U$1") (pin "P9.5") (pinfunction "VDD_5V_P9.5") (pintype "bidirectional"))
    )
    (net (code "181") (name "unconnected-(U$1B-VDD_5V-PadP9.6)") (class "Default")
      (node (ref "U$1") (pin "P9.6") (pinfunction "VDD_5V_P9.6") (pintype "bidirectional"))
    )
    (net (code "182") (name "unconnected-(U$1B-VDD_ADC-PadP9.32)") (class "Default")
      (node (ref "U$1") (pin "P9.32") (pinfunction "VDD_ADC_P9.32") (pintype "bidirectional"))
    )
    (net (code "183") (name "unconnected-(U3-OUT-Pad2)") (class "Default")
      (node (ref "U3") (pin "2") (pinfunction "OUT_2") (pintype "output"))
    )
  )
)
